# lia.net
KiCad netlist of a schematic drawn in EAGLE
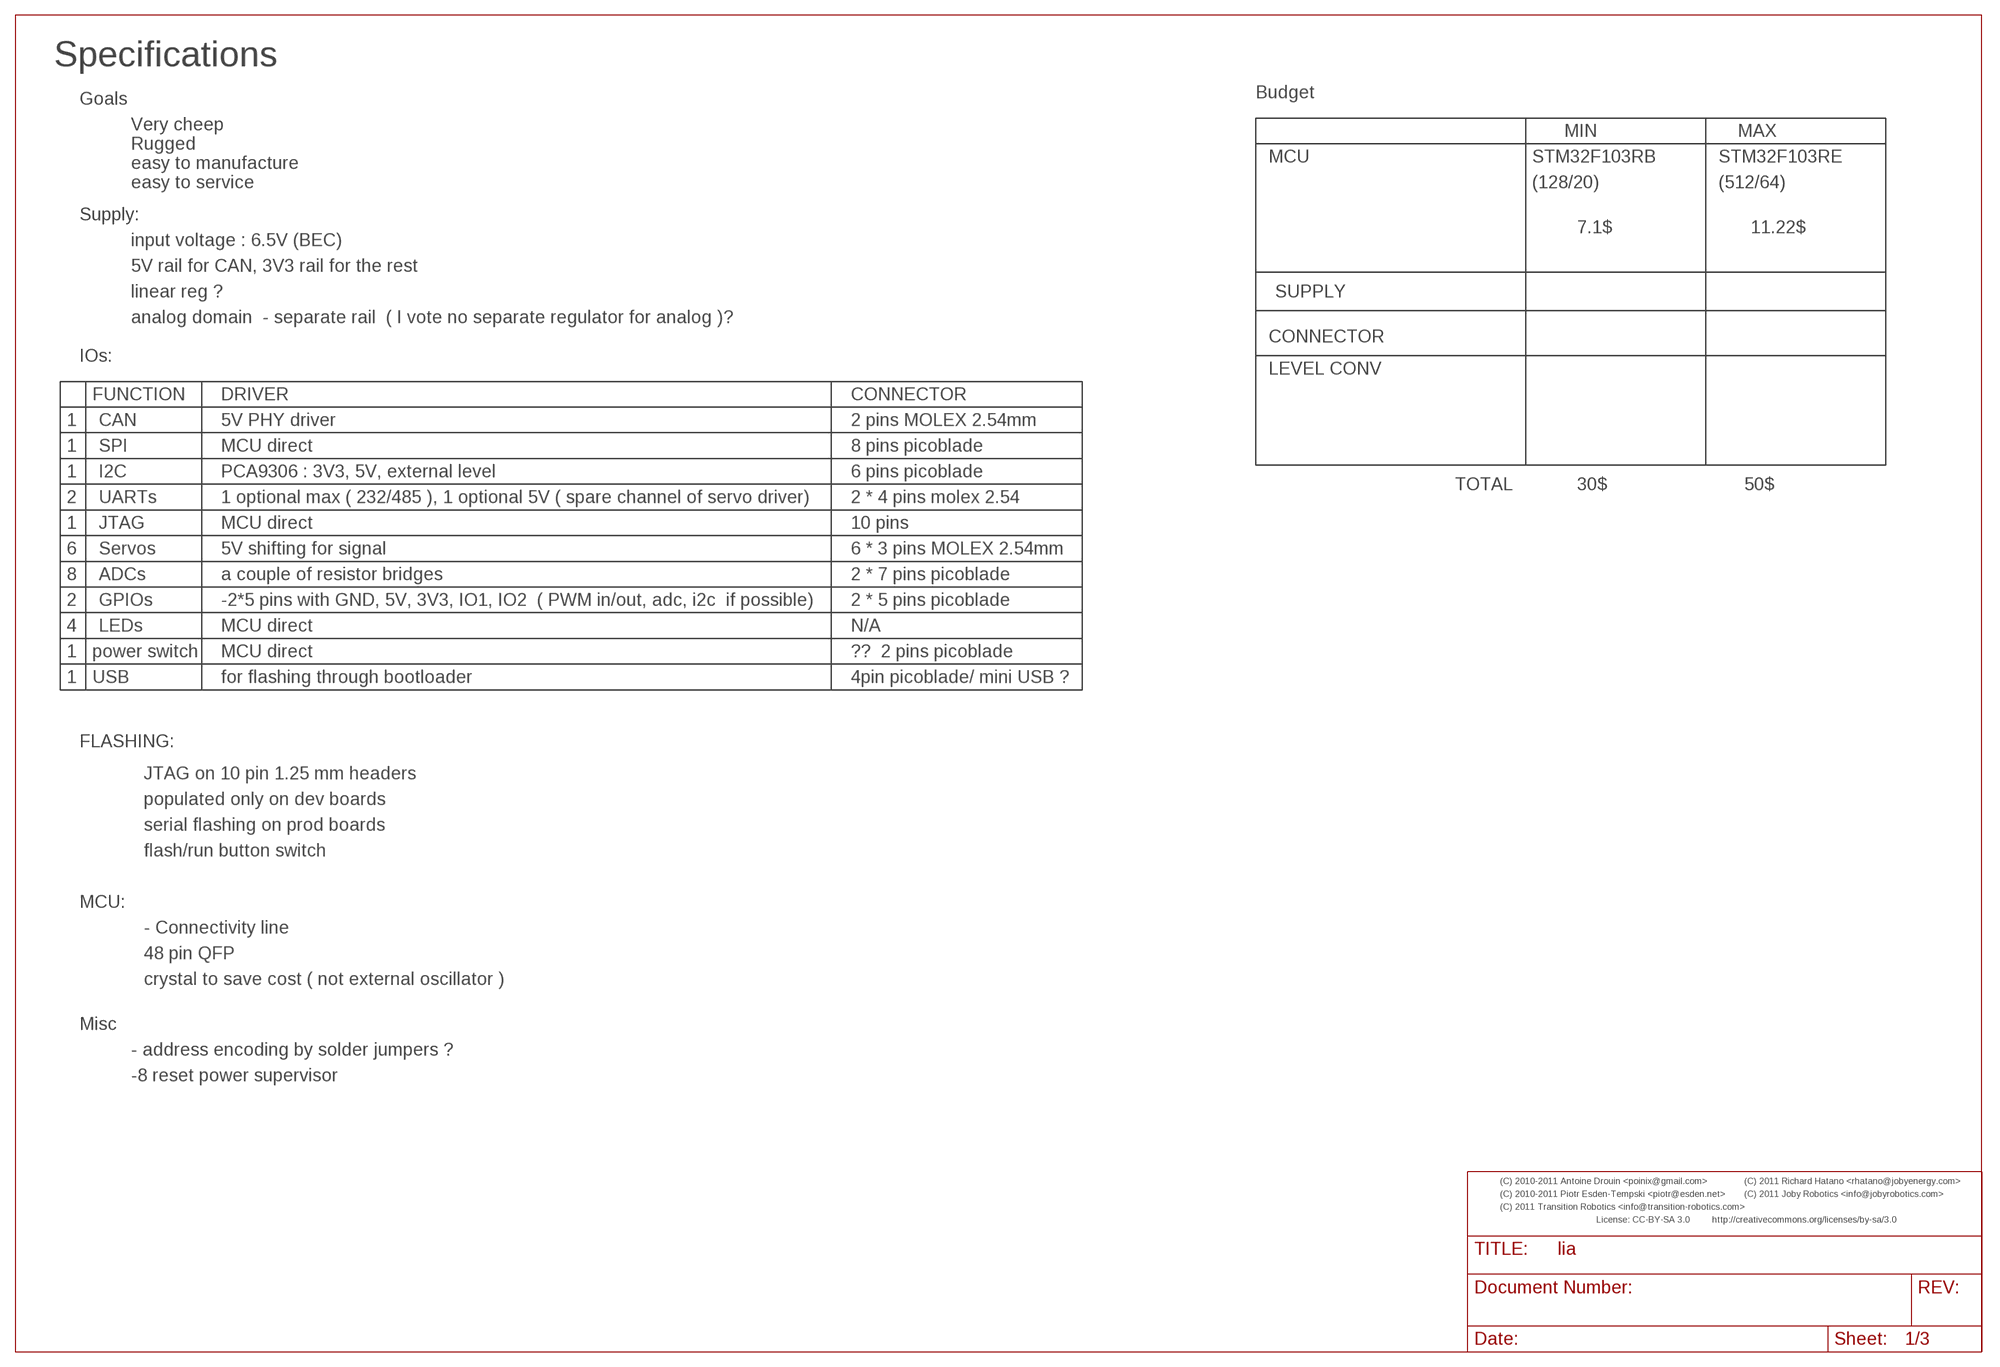
[diagram p0: schematic, sheet 1]
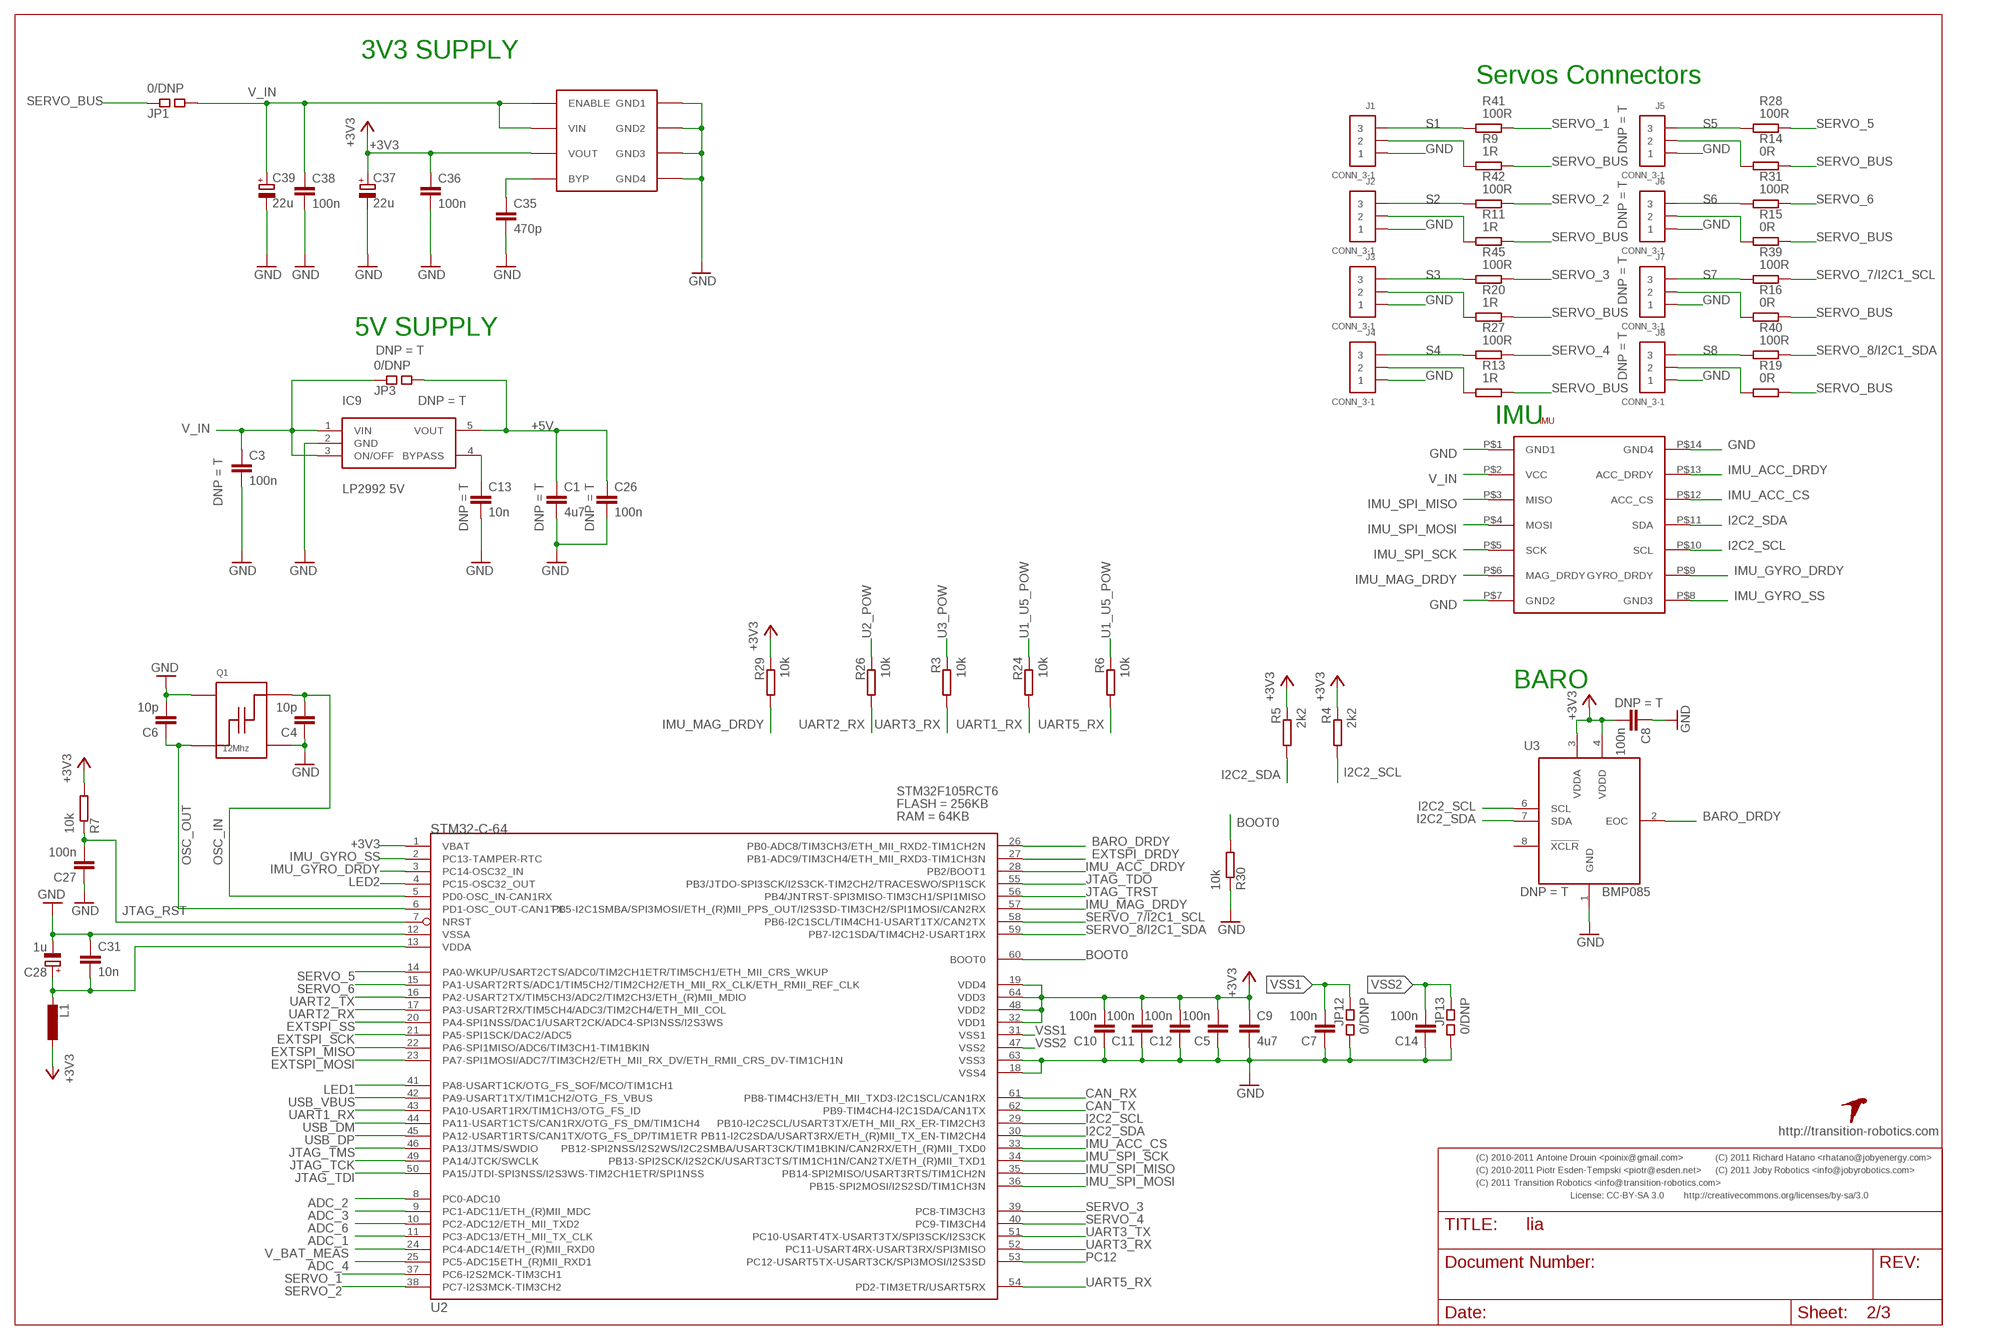
[diagram p1: schematic, sheet 2]
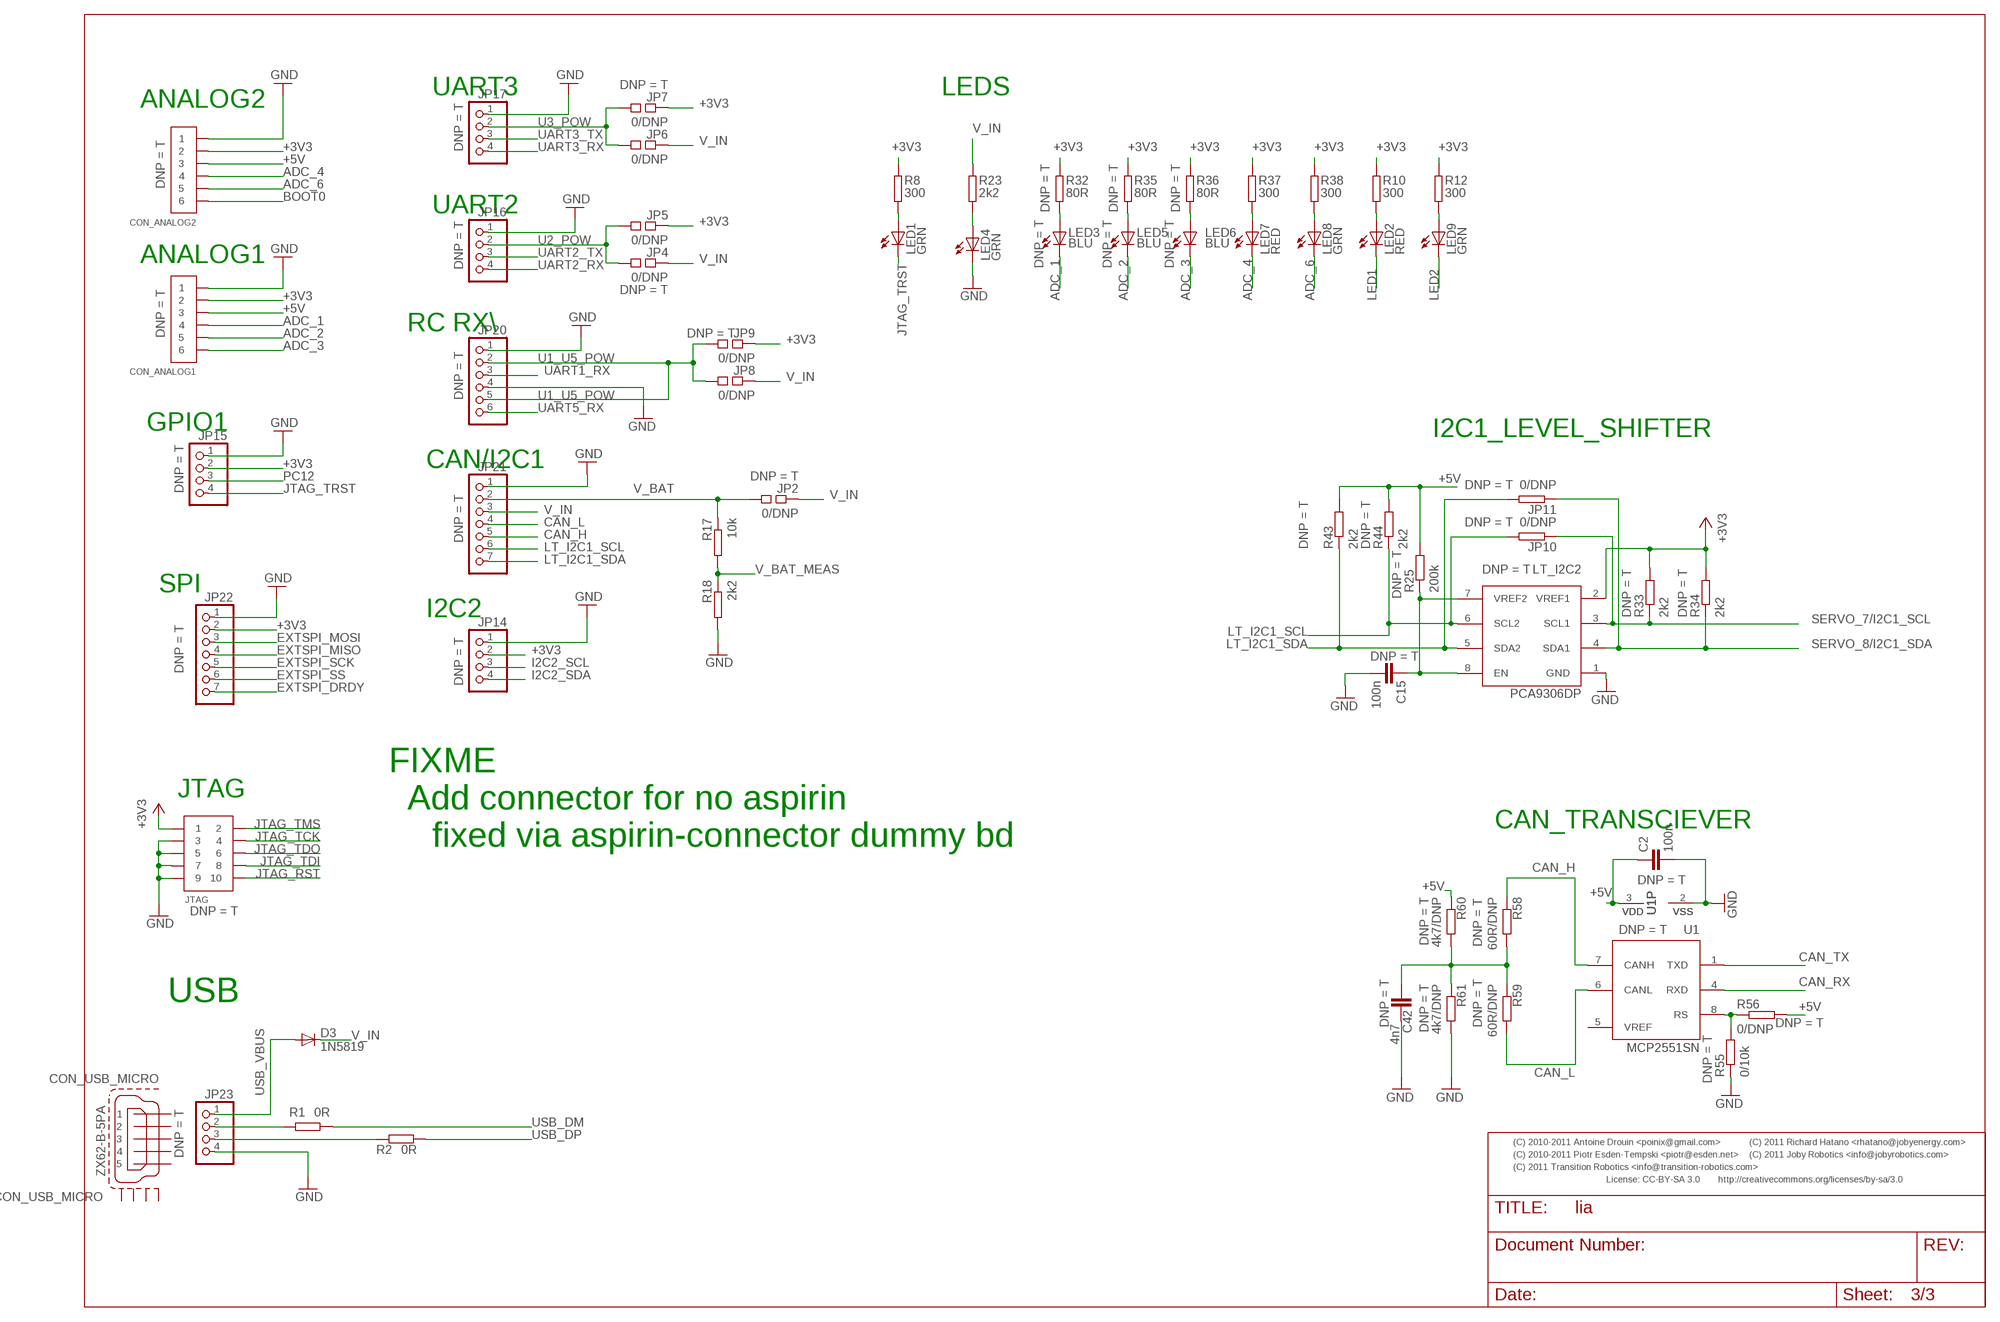
[diagram p2: schematic, sheet 3]

(export (version "E")
  (design (tool "Eeschema 10.0.6"))
  (components
    (comp (ref "C1")
      (value "4u7")
      (footprint "eagle-import:0805-CAP")
      (fields (field (name "DNP") "T") (field (name "PARTNO") "cap-cer-0805-4u7"))
      (libsource (lib "eagle-import") (part "CAPACITOR-0805"))
    )
    (comp (ref "C3")
      (value "100n")
      (footprint "eagle-import:0603-CAP")
      (fields (field (name "DNP") "T") (field (name "PARTNO") "cap-cer-0603-100n"))
      (libsource (lib "eagle-import") (part "CAPACITOR-0603"))
    )
    (comp (ref "C4")
      (value "10p")
      (footprint "eagle-import:0402-CAP")
      (fields (field (name "PARTNO") "cap-cer-0402-10p"))
      (libsource (lib "eagle-import") (part "CAPACITOR-0402"))
    )
    (comp (ref "C5")
      (value "100n")
      (footprint "eagle-import:0402-CAP")
      (fields (field (name "PARTNO") "cap-cer-0402-100n"))
      (libsource (lib "eagle-import") (part "CAPACITOR-0402"))
    )
    (comp (ref "C6")
      (value "10p")
      (footprint "eagle-import:0402-CAP")
      (fields (field (name "PARTNO") "cap-cer-0402-10p"))
      (libsource (lib "eagle-import") (part "CAPACITOR-0402"))
    )
    (comp (ref "C7")
      (value "100n")
      (footprint "eagle-import:0402-CAP")
      (fields (field (name "PARTNO") "cap-cer-0402-100n"))
      (libsource (lib "eagle-import") (part "CAPACITOR-0402"))
    )
    (comp (ref "C8")
      (value "100n")
      (footprint "eagle-import:0402-CAP")
      (fields (field (name "DNP") "T") (field (name "PARTNO") "cap-cer-0402-100n"))
      (libsource (lib "eagle-import") (part "CAPACITOR-0402"))
    )
    (comp (ref "C9")
      (value "4u7")
      (footprint "eagle-import:0805-CAP")
      (fields (field (name "PARTNO") "cap-cer-0805-4u7"))
      (libsource (lib "eagle-import") (part "CAPACITOR-0805"))
    )
    (comp (ref "C10")
      (value "100n")
      (footprint "eagle-import:0402-CAP")
      (fields (field (name "PARTNO") "cap-cer-0402-100n"))
      (libsource (lib "eagle-import") (part "CAPACITOR-0402"))
    )
    (comp (ref "C11")
      (value "100n")
      (footprint "eagle-import:0402-CAP")
      (fields (field (name "PARTNO") "cap-cer-0402-100n"))
      (libsource (lib "eagle-import") (part "CAPACITOR-0402"))
    )
    (comp (ref "C12")
      (value "100n")
      (footprint "eagle-import:0402-CAP")
      (fields (field (name "PARTNO") "cap-cer-0402-100n"))
      (libsource (lib "eagle-import") (part "CAPACITOR-0402"))
    )
    (comp (ref "C13")
      (value "10n")
      (footprint "eagle-import:0402-CAP")
      (fields (field (name "DNP") "T") (field (name "PARTNO") "cap-cer-0402-10n"))
      (libsource (lib "eagle-import") (part "CAPACITOR-0402"))
    )
    (comp (ref "C14")
      (value "100n")
      (footprint "eagle-import:0402-CAP")
      (fields (field (name "PARTNO") "cap-cer-0402-100n"))
      (libsource (lib "eagle-import") (part "CAPACITOR-0402"))
    )
    (comp (ref "C26")
      (value "100n")
      (footprint "eagle-import:0603-CAP")
      (fields (field (name "DNP") "T") (field (name "PARTNO") "cap-cer-0603-100n"))
      (libsource (lib "eagle-import") (part "CAPACITOR-0603"))
    )
    (comp (ref "C27")
      (value "100n")
      (footprint "eagle-import:0402-CAP")
      (fields (field (name "PARTNO") "cap-cer-0402-100n"))
      (libsource (lib "eagle-import") (part "CAPACITOR-0402"))
    )
    (comp (ref "C28")
      (value "1u")
      (footprint "eagle-import:0603-POL-CAP")
      (fields (field (name "PARTNO") "cap-tan-0603-1u"))
      (libsource (lib "eagle-import") (part "CAPACITOR-POL-0603"))
    )
    (comp (ref "C31")
      (value "10n")
      (footprint "eagle-import:0402-CAP")
      (fields (field (name "PARTNO") "cap-cer-0402-10n"))
      (libsource (lib "eagle-import") (part "CAPACITOR-0402"))
    )
    (comp (ref "C35")
      (value "470p")
      (footprint "eagle-import:0402-CAP")
      (fields (field (name "PARTNO") "cap-cer-0402-470p"))
      (libsource (lib "eagle-import") (part "CAPACITOR-0402"))
    )
    (comp (ref "C36")
      (value "100n")
      (footprint "eagle-import:0603-CAP")
      (fields (field (name "PARTNO") "cap-cer-0603-100n"))
      (libsource (lib "eagle-import") (part "CAPACITOR-0603"))
    )
    (comp (ref "C37")
      (value "22u")
      (footprint "eagle-import:3528_B")
      (fields (field (name "PARTNO") "cap-tan-B-22u-16v"))
      (libsource (lib "eagle-import") (part "CAPACITOR-POLB"))
    )
    (comp (ref "C38")
      (value "100n")
      (footprint "eagle-import:0402-CAP")
      (fields (field (name "PARTNO") "cap-cer-0402-100n"))
      (libsource (lib "eagle-import") (part "CAPACITOR-0402"))
    )
    (comp (ref "C39")
      (value "22u")
      (footprint "eagle-import:3528_B")
      (fields (field (name "PARTNO") "cap-tan-B-22u-16v"))
      (libsource (lib "eagle-import") (part "CAPACITOR-POLB"))
    )
    (comp (ref "IC9")
      (value "LP2992 5V")
      (footprint "eagle-import:SOT23-5")
      (fields (field (name "DNP") "T") (field (name "PARTNO") "vreg-sot-23-5-5v"))
      (libsource (lib "eagle-import") (part "LP2992"))
    )
    (comp (ref "IMU")
      (value "ASPIRIN")
      (footprint "eagle-import:ASPIRIN_1")
      (fields (field (name "PARTNO") "pcb-ass-aspirin"))
      (libsource (lib "eagle-import") (part "ASPIRIN"))
    )
    (comp (ref "J1")
      (value "CONN_3-1")
      (footprint "eagle-import:SIP1X3_100")
      (fields (field (name "PARTNO") "conn-th-0.1in-3-2-ra"))
      (libsource (lib "eagle-import") (part "CONN_3-1"))
    )
    (comp (ref "J2")
      (value "CONN_3-1")
      (footprint "eagle-import:SIP1X3_100")
      (fields (field (name "PARTNO") "conn-th-0.1in-3-2-ra"))
      (libsource (lib "eagle-import") (part "CONN_3-1"))
    )
    (comp (ref "J3")
      (value "CONN_3-1")
      (footprint "eagle-import:SIP1X3_100")
      (fields (field (name "PARTNO") "conn-th-0.1in-3-2-ra"))
      (libsource (lib "eagle-import") (part "CONN_3-1"))
    )
    (comp (ref "J4")
      (value "CONN_3-1")
      (footprint "eagle-import:SIP1X3_100")
      (fields (field (name "PARTNO") "conn-th-0.1in-3-2-ra"))
      (libsource (lib "eagle-import") (part "CONN_3-1"))
    )
    (comp (ref "J5")
      (value "CONN_3-1")
      (footprint "eagle-import:SIP1X3_100")
      (fields (field (name "DNP") "T") (field (name "PARTNO") "conn-th-0.1in-3-2-ra"))
      (libsource (lib "eagle-import") (part "CONN_3-1"))
    )
    (comp (ref "J6")
      (value "CONN_3-1")
      (footprint "eagle-import:SIP1X3_100")
      (fields (field (name "DNP") "T") (field (name "PARTNO") "conn-th-0.1in-3-2-ra"))
      (libsource (lib "eagle-import") (part "CONN_3-1"))
    )
    (comp (ref "J7")
      (value "CONN_3-1")
      (footprint "eagle-import:SIP1X3_100")
      (fields (field (name "DNP") "T") (field (name "PARTNO") "conn-th-0.1in-3-2-ra"))
      (libsource (lib "eagle-import") (part "CONN_3-1"))
    )
    (comp (ref "J8")
      (value "CONN_3-1")
      (footprint "eagle-import:SIP1X3_100")
      (fields (field (name "DNP") "T") (field (name "PARTNO") "conn-th-0.1in-3-2-ra"))
      (libsource (lib "eagle-import") (part "CONN_3-1"))
    )
    (comp (ref "JP1")
      (value "0/DNP")
      (footprint "eagle-import:0402-SQJMP")
      (fields (field (name "PARTNO") "res-0402-0"))
      (libsource (lib "eagle-import") (part "SQ_JMP-0402"))
    )
    (comp (ref "JP3")
      (value "0/DNP")
      (footprint "eagle-import:0402-SQJMP")
      (fields (field (name "DNP") "T") (field (name "PARTNO") "res-0402-0"))
      (libsource (lib "eagle-import") (part "SQ_JMP-0402"))
    )
    (comp (ref "JP12")
      (value "0/DNP")
      (footprint "eagle-import:0402-SQJMP")
      (fields (field (name "PARTNO") "res-0402-0"))
      (libsource (lib "eagle-import") (part "SQ_JMP-0402"))
    )
    (comp (ref "JP13")
      (value "0/DNP")
      (footprint "eagle-import:0402-SQJMP")
      (fields (field (name "PARTNO") "res-0402-0"))
      (libsource (lib "eagle-import") (part "SQ_JMP-0402"))
    )
    (comp (ref "L1")
      (value "INDUCTOR-0603")
      (footprint "eagle-import:0603-IND")
      (fields (field (name "PARTNO") "ferrite-0603-600ohm"))
      (libsource (lib "eagle-import") (part "INDUCTOR-0603"))
    )
    (comp (ref "Q1")
      (value "12Mhz")
      (footprint "eagle-import:ABM8")
      (fields (field (name "PARTNO") "xtal-abm8-12mhz"))
      (libsource (lib "eagle-import") (part "ABM8"))
    )
    (comp (ref "R3")
      (value "10k")
      (footprint "eagle-import:0402-RES")
      (fields (field (name "PARTNO") "res-0402-10k"))
      (libsource (lib "eagle-import") (part "RESISTOR-0402"))
    )
    (comp (ref "R4")
      (value "2k2")
      (footprint "eagle-import:0402-RES")
      (fields (field (name "PARTNO") "res-0402-2k2"))
      (libsource (lib "eagle-import") (part "RESISTOR-0402"))
    )
    (comp (ref "R5")
      (value "2k2")
      (footprint "eagle-import:0402-RES")
      (fields (field (name "PARTNO") "res-0402-2k2"))
      (libsource (lib "eagle-import") (part "RESISTOR-0402"))
    )
    (comp (ref "R6")
      (value "10k")
      (footprint "eagle-import:0402-RES")
      (fields (field (name "PARTNO") "res-0402-10k"))
      (libsource (lib "eagle-import") (part "RESISTOR-0402"))
    )
    (comp (ref "R7")
      (value "10k")
      (footprint "eagle-import:0402-RES")
      (fields (field (name "PARTNO") "res-0402-10k"))
      (libsource (lib "eagle-import") (part "RESISTOR-0402"))
    )
    (comp (ref "R9")
      (value "1R")
      (footprint "eagle-import:1206-RES")
      (fields (field (name "PARTNO") "res-1206-1"))
      (libsource (lib "eagle-import") (part "RESISTOR-1206"))
    )
    (comp (ref "R11")
      (value "1R")
      (footprint "eagle-import:1206-RES")
      (fields (field (name "PARTNO") "res-1206-1"))
      (libsource (lib "eagle-import") (part "RESISTOR-1206"))
    )
    (comp (ref "R13")
      (value "1R")
      (footprint "eagle-import:1206-RES")
      (fields (field (name "PARTNO") "res-1206-1"))
      (libsource (lib "eagle-import") (part "RESISTOR-1206"))
    )
    (comp (ref "R14")
      (value "0R")
      (footprint "eagle-import:1206-RES")
      (fields (field (name "PARTNO") "res-1206-0"))
      (libsource (lib "eagle-import") (part "RESISTOR-1206"))
    )
    (comp (ref "R15")
      (value "0R")
      (footprint "eagle-import:1206-RES")
      (fields (field (name "PARTNO") "res-1206-0"))
      (libsource (lib "eagle-import") (part "RESISTOR-1206"))
    )
    (comp (ref "R16")
      (value "0R")
      (footprint "eagle-import:1206-RES")
      (fields (field (name "PARTNO") "res-1206-0"))
      (libsource (lib "eagle-import") (part "RESISTOR-1206"))
    )
    (comp (ref "R19")
      (value "0R")
      (footprint "eagle-import:1206-RES")
      (fields (field (name "PARTNO") "res-1206-0"))
      (libsource (lib "eagle-import") (part "RESISTOR-1206"))
    )
    (comp (ref "R20")
      (value "1R")
      (footprint "eagle-import:1206-RES")
      (fields (field (name "PARTNO") "res-1206-1"))
      (libsource (lib "eagle-import") (part "RESISTOR-1206"))
    )
    (comp (ref "R24")
      (value "10k")
      (footprint "eagle-import:0402-RES")
      (fields (field (name "PARTNO") "res-0402-10k"))
      (libsource (lib "eagle-import") (part "RESISTOR-0402"))
    )
    (comp (ref "R26")
      (value "10k")
      (footprint "eagle-import:0402-RES")
      (fields (field (name "PARTNO") "res-0402-10k"))
      (libsource (lib "eagle-import") (part "RESISTOR-0402"))
    )
    (comp (ref "R27")
      (value "100R")
      (footprint "eagle-import:0402-RES")
      (fields (field (name "PARTNO") "res-0402-100"))
      (libsource (lib "eagle-import") (part "RESISTOR-0402"))
    )
    (comp (ref "R28")
      (value "100R")
      (footprint "eagle-import:0402-RES")
      (fields (field (name "PARTNO") "res-0402-100"))
      (libsource (lib "eagle-import") (part "RESISTOR-0402"))
    )
    (comp (ref "R29")
      (value "10k")
      (footprint "eagle-import:0402-RES")
      (fields (field (name "PARTNO") "res-0402-10k"))
      (libsource (lib "eagle-import") (part "RESISTOR-0402"))
    )
    (comp (ref "R30")
      (value "10k")
      (footprint "eagle-import:0402-RES")
      (fields (field (name "PARTNO") "res-0402-10k"))
      (libsource (lib "eagle-import") (part "RESISTOR-0402"))
    )
    (comp (ref "R31")
      (value "100R")
      (footprint "eagle-import:0402-RES")
      (fields (field (name "PARTNO") "res-0402-100"))
      (libsource (lib "eagle-import") (part "RESISTOR-0402"))
    )
    (comp (ref "R39")
      (value "100R")
      (footprint "eagle-import:0402-RES")
      (fields (field (name "PARTNO") "res-0402-100"))
      (libsource (lib "eagle-import") (part "RESISTOR-0402"))
    )
    (comp (ref "R40")
      (value "100R")
      (footprint "eagle-import:0402-RES")
      (fields (field (name "PARTNO") "res-0402-100"))
      (libsource (lib "eagle-import") (part "RESISTOR-0402"))
    )
    (comp (ref "R41")
      (value "100R")
      (footprint "eagle-import:0402-RES")
      (fields (field (name "PARTNO") "res-0402-100"))
      (libsource (lib "eagle-import") (part "RESISTOR-0402"))
    )
    (comp (ref "R42")
      (value "100R")
      (footprint "eagle-import:0402-RES")
      (fields (field (name "PARTNO") "res-0402-100"))
      (libsource (lib "eagle-import") (part "RESISTOR-0402"))
    )
    (comp (ref "R45")
      (value "100R")
      (footprint "eagle-import:0402-RES")
      (fields (field (name "PARTNO") "res-0402-100"))
      (libsource (lib "eagle-import") (part "RESISTOR-0402"))
    )
    (comp (ref "U$1")
      (value "TR-LOGO")
      (footprint "eagle-import:TR-LOGO")
      (libsource (lib "eagle-import") (part "TR-LOGO"))
    )
    (comp (ref "U2")
      (value "STM32-C-64")
      (footprint "eagle-import:LQFP64")
      (fields
        (field (name "FLASH") "256KB")
        (field (name "PARTNO") "mcu-lqfp-64-stm32")
        (field (name "PART_NR") "STM32F105RCT6")
        (field (name "RAM") "64KB")
      )
      (libsource (lib "eagle-import") (part "STM32-C-64"))
    )
    (comp (ref "U3")
      (value "BMP085")
      (footprint "eagle-import:LCC8")
      (fields (field (name "DNP") "T") (field (name "PARTNO") "sensr-clcc-8-baro"))
      (libsource (lib "eagle-import") (part "BMP085"))
    )
    (comp (ref "VREG1")
      (value "MIC5209")
      (footprint "eagle-import:SOIC8")
      (fields (field (name "PARTNO") "vreg-so8-3v3"))
      (libsource (lib "eagle-import") (part "MIC5209"))
    )
    (comp (ref "C2")
      (value "100n")
      (footprint "eagle-import:0402-CAP")
      (fields (field (name "DNP") "T") (field (name "PARTNO") "cap-cer-0402-100n"))
      (libsource (lib "eagle-import") (part "CAPACITOR-0402"))
    )
    (comp (ref "C15")
      (value "100n")
      (footprint "eagle-import:0402-CAP")
      (fields (field (name "DNP") "T") (field (name "PARTNO") "cap-cer-0402-100n"))
      (libsource (lib "eagle-import") (part "CAPACITOR-0402"))
    )
    (comp (ref "C42")
      (value "4n7")
      (footprint "eagle-import:0603-CAP")
      (fields (field (name "DNP") "T") (field (name "PARTNO") "cap-cer-0603-4n7"))
      (libsource (lib "eagle-import") (part "CAPACITOR-0603"))
    )
    (comp (ref "CON_ANALOG1")
      (value "CONN_6-1-53398")
      (footprint "eagle-import:PB-53398-06")
      (fields (field (name "DNP") "T") (field (name "PARTNO") "conn-picoblade-smd-0.05in-6-vert"))
      (libsource (lib "eagle-import") (part "CONN_6-1-53398"))
    )
    (comp (ref "CON_ANALOG2")
      (value "CONN_6-1-53398")
      (footprint "eagle-import:PB-53398-06")
      (fields (field (name "DNP") "T") (field (name "PARTNO") "conn-picoblade-smd-0.05in-6-vert"))
      (libsource (lib "eagle-import") (part "CONN_6-1-53398"))
    )
    (comp (ref "CON_USB_MICRO")
      (value "ZX62-B-5PA")
      (footprint "eagle-import:ZX62-B-5PA")
      (fields (field (name "PARTNO") "conn-smd-usb-micro-b"))
      (libsource (lib "eagle-import") (part "ZX62-B-5PA"))
    )
    (comp (ref "D3")
      (value "1N5819")
      (footprint "eagle-import:MICROMELF-R")
      (fields (field (name "PARTNO") "diode-schottky-1608"))
      (libsource (lib "eagle-import") (part "DIODE-MICROMELF-R"))
    )
    (comp (ref "JP2")
      (value "0/DNP")
      (footprint "eagle-import:0402-SQJMP")
      (fields (field (name "DNP") "T") (field (name "PARTNO") "res-0402-0"))
      (libsource (lib "eagle-import") (part "SQ_JMP-0402"))
    )
    (comp (ref "JP4")
      (value "0/DNP")
      (footprint "eagle-import:0402-SQJMP")
      (fields (field (name "DNP") "T") (field (name "PARTNO") "res-0402-0"))
      (libsource (lib "eagle-import") (part "SQ_JMP-0402"))
    )
    (comp (ref "JP5")
      (value "0/DNP")
      (footprint "eagle-import:0402-SQJMP")
      (fields (field (name "PARTNO") "res-0402-0"))
      (libsource (lib "eagle-import") (part "SQ_JMP-0402"))
    )
    (comp (ref "JP6")
      (value "0/DNP")
      (footprint "eagle-import:0402-SQJMP")
      (fields (field (name "PARTNO") "res-0402-0"))
      (libsource (lib "eagle-import") (part "SQ_JMP-0402"))
    )
    (comp (ref "JP7")
      (value "0/DNP")
      (footprint "eagle-import:0402-SQJMP")
      (fields (field (name "DNP") "T") (field (name "PARTNO") "res-0402-0"))
      (libsource (lib "eagle-import") (part "SQ_JMP-0402"))
    )
    (comp (ref "JP8")
      (value "0/DNP")
      (footprint "eagle-import:0402-SQJMP")
      (fields (field (name "PARTNO") "res-0402-0"))
      (libsource (lib "eagle-import") (part "SQ_JMP-0402"))
    )
    (comp (ref "JP9")
      (value "0/DNP")
      (footprint "eagle-import:0402-SQJMP")
      (fields (field (name "DNP") "T") (field (name "PARTNO") "res-0402-0"))
      (libsource (lib "eagle-import") (part "SQ_JMP-0402"))
    )
    (comp (ref "JP10")
      (value "0/DNP")
      (footprint "eagle-import:0603-RES")
      (fields (field (name "DNP") "T") (field (name "PARTNO") "res-0603-0"))
      (libsource (lib "eagle-import") (part "RESISTOR-0603"))
    )
    (comp (ref "JP11")
      (value "0/DNP")
      (footprint "eagle-import:0603-RES")
      (fields (field (name "DNP") "T") (field (name "PARTNO") "res-0603-0"))
      (libsource (lib "eagle-import") (part "RESISTOR-0603"))
    )
    (comp (ref "JP14")
      (value "PINHD-1X4")
      (footprint "eagle-import:1X04")
      (fields (field (name "DNP") "T") (field (name "PARTNO") "conn-th-0.1in-4-1"))
      (libsource (lib "eagle-import") (part "PINHD-1X4"))
    )
    (comp (ref "JP15")
      (value "PINHD-1X4")
      (footprint "eagle-import:1X04")
      (fields (field (name "DNP") "T") (field (name "PARTNO") "conn-th-0.1in-4-1"))
      (libsource (lib "eagle-import") (part "PINHD-1X4"))
    )
    (comp (ref "JP16")
      (value "PINHD-1X4")
      (footprint "eagle-import:1X04")
      (fields (field (name "DNP") "T") (field (name "PARTNO") "conn-th-0.1in-4-1"))
      (libsource (lib "eagle-import") (part "PINHD-1X4"))
    )
    (comp (ref "JP17")
      (value "PINHD-1X4")
      (footprint "eagle-import:1X04")
      (fields (field (name "DNP") "T") (field (name "PARTNO") "conn-th-0.1in-4-1"))
      (libsource (lib "eagle-import") (part "PINHD-1X4"))
    )
    (comp (ref "JP20")
      (value "PINHD-1X6")
      (footprint "eagle-import:1X06")
      (fields (field (name "DNP") "T") (field (name "PARTNO") "conn-th-0.1in-6-1"))
      (libsource (lib "eagle-import") (part "PINHD-1X6"))
    )
    (comp (ref "JP21")
      (value "PINHD-1X7")
      (footprint "eagle-import:1X07")
      (fields (field (name "DNP") "T") (field (name "PARTNO") "conn-th-0.1in-7-1"))
      (libsource (lib "eagle-import") (part "PINHD-1X7"))
    )
    (comp (ref "JP22")
      (value "PINHD-1X7")
      (footprint "eagle-import:1X07")
      (fields (field (name "DNP") "T") (field (name "PARTNO") "conn-th-0.1in-7-1"))
      (libsource (lib "eagle-import") (part "PINHD-1X7"))
    )
    (comp (ref "JP23")
      (value "PINHD-1X4")
      (footprint "eagle-import:1X04")
      (fields (field (name "DNP") "T") (field (name "PARTNO") "conn-th-0.1in-4-1"))
      (libsource (lib "eagle-import") (part "PINHD-1X4"))
    )
    (comp (ref "JTAG")
      (value "PIN_HDR_EDG_1.27MM_5-2")
      (footprint "eagle-import:FTSH-105-DV")
      (fields (field (name "DNP") "T") (field (name "PARTNO") "conn-smd-0.05in-5-2"))
      (libsource (lib "eagle-import") (part "CONN_5-2-FTSH-V"))
    )
    (comp (ref "LED1")
      (value "GRN")
      (footprint "eagle-import:0402-LED")
      (fields (field (name "PARTNO") "led-0402-green"))
      (libsource (lib "eagle-import") (part "LED-0402"))
    )
    (comp (ref "LED2")
      (value "RED")
      (footprint "eagle-import:0402-LED")
      (fields (field (name "PARTNO") "led-0402-red"))
      (libsource (lib "eagle-import") (part "LED-0402"))
    )
    (comp (ref "LED3")
      (value "BLU")
      (footprint "eagle-import:0402-LED")
      (fields (field (name "DNP") "T") (field (name "PARTNO") "led-0402-blue"))
      (libsource (lib "eagle-import") (part "LED-0402"))
    )
    (comp (ref "LED4")
      (value "GRN")
      (footprint "eagle-import:0402-LED")
      (fields (field (name "PARTNO") "led-0402-green"))
      (libsource (lib "eagle-import") (part "LED-0402"))
    )
    (comp (ref "LED5")
      (value "BLU")
      (footprint "eagle-import:0402-LED")
      (fields (field (name "DNP") "T") (field (name "PARTNO") "led-0402-blue"))
      (libsource (lib "eagle-import") (part "LED-0402"))
    )
    (comp (ref "LED6")
      (value "BLU")
      (footprint "eagle-import:0402-LED")
      (fields (field (name "DNP") "T") (field (name "PARTNO") "led-0402-blue"))
      (libsource (lib "eagle-import") (part "LED-0402"))
    )
    (comp (ref "LED7")
      (value "RED")
      (footprint "eagle-import:0402-LED")
      (fields (field (name "PARTNO") "led-0402-red"))
      (libsource (lib "eagle-import") (part "LED-0402"))
    )
    (comp (ref "LED8")
      (value "GRN")
      (footprint "eagle-import:0402-LED")
      (fields (field (name "PARTNO") "led-0402-green"))
      (libsource (lib "eagle-import") (part "LED-0402"))
    )
    (comp (ref "LED9")
      (value "GRN")
      (footprint "eagle-import:0402-LED")
      (fields (field (name "PARTNO") "led-0402-green"))
      (libsource (lib "eagle-import") (part "LED-0402"))
    )
    (comp (ref "LT_I2C2")
      (value "PCA9306DP")
      (footprint "eagle-import:TSSOP_B3")
      (fields (field (name "DNP") "T") (field (name "PARTNO") "ic-tssop8-level-trans"))
      (libsource (lib "eagle-import") (part "PCA9306DP"))
    )
    (comp (ref "R1")
      (value "0R")
      (footprint "eagle-import:0402-RES")
      (fields (field (name "PARTNO") "res-0402-0"))
      (libsource (lib "eagle-import") (part "RESISTOR-0402"))
    )
    (comp (ref "R2")
      (value "0R")
      (footprint "eagle-import:0402-RES")
      (fields (field (name "PARTNO") "res-0402-0"))
      (libsource (lib "eagle-import") (part "RESISTOR-0402"))
    )
    (comp (ref "R8")
      (value "300")
      (footprint "eagle-import:0402-RES")
      (fields (field (name "PARTNO") "res-0402-300"))
      (libsource (lib "eagle-import") (part "RESISTOR-0402"))
    )
    (comp (ref "R10")
      (value "300")
      (footprint "eagle-import:0402-RES")
      (fields (field (name "PARTNO") "res-0402-300"))
      (libsource (lib "eagle-import") (part "RESISTOR-0402"))
    )
    (comp (ref "R12")
      (value "300")
      (footprint "eagle-import:0402-RES")
      (fields (field (name "PARTNO") "res-0402-300"))
      (libsource (lib "eagle-import") (part "RESISTOR-0402"))
    )
    (comp (ref "R17")
      (value "10k")
      (footprint "eagle-import:0402-RES")
      (fields (field (name "PARTNO") "res-0402-10k"))
      (libsource (lib "eagle-import") (part "RESISTOR-0402"))
    )
    (comp (ref "R18")
      (value "2k2")
      (footprint "eagle-import:0402-RES")
      (fields (field (name "PARTNO") "res-0402-2k2"))
      (libsource (lib "eagle-import") (part "RESISTOR-0402"))
    )
    (comp (ref "R23")
      (value "2k2")
      (footprint "eagle-import:0402-RES")
      (fields (field (name "PARTNO") "res-0402-2k2"))
      (libsource (lib "eagle-import") (part "RESISTOR-0402"))
    )
    (comp (ref "R25")
      (value "200k")
      (footprint "eagle-import:0402-RES")
      (fields (field (name "DNP") "T") (field (name "PARTNO") "res-0402-200k"))
      (libsource (lib "eagle-import") (part "RESISTOR-0402"))
    )
    (comp (ref "R32")
      (value "80R")
      (footprint "eagle-import:0402-RES")
      (fields (field (name "DNP") "T") (field (name "PARTNO") "res-0402-80"))
      (libsource (lib "eagle-import") (part "RESISTOR-0402"))
    )
    (comp (ref "R33")
      (value "2k2")
      (footprint "eagle-import:0402-RES")
      (fields (field (name "DNP") "T") (field (name "PARTNO") "res-0402-2k2"))
      (libsource (lib "eagle-import") (part "RESISTOR-0402"))
    )
    (comp (ref "R34")
      (value "2k2")
      (footprint "eagle-import:0402-RES")
      (fields (field (name "DNP") "T") (field (name "PARTNO") "res-0402-2k2"))
      (libsource (lib "eagle-import") (part "RESISTOR-0402"))
    )
    (comp (ref "R35")
      (value "80R")
      (footprint "eagle-import:0402-RES")
      (fields (field (name "DNP") "T") (field (name "PARTNO") "res-0402-80"))
      (libsource (lib "eagle-import") (part "RESISTOR-0402"))
    )
    (comp (ref "R36")
      (value "80R")
      (footprint "eagle-import:0402-RES")
      (fields (field (name "DNP") "T") (field (name "PARTNO") "res-0402-80"))
      (libsource (lib "eagle-import") (part "RESISTOR-0402"))
    )
    (comp (ref "R37")
      (value "300")
      (footprint "eagle-import:0402-RES")
      (fields (field (name "PARTNO") "res-0402-300"))
      (libsource (lib "eagle-import") (part "RESISTOR-0402"))
    )
    (comp (ref "R38")
      (value "300")
      (footprint "eagle-import:0402-RES")
      (fields (field (name "PARTNO") "res-0402-300"))
      (libsource (lib "eagle-import") (part "RESISTOR-0402"))
    )
    (comp (ref "R43")
      (value "2k2")
      (footprint "eagle-import:0402-RES")
      (fields (field (name "DNP") "T") (field (name "PARTNO") "res-0402-1k5"))
      (libsource (lib "eagle-import") (part "RESISTOR-0402"))
    )
    (comp (ref "R44")
      (value "2k2")
      (footprint "eagle-import:0402-RES")
      (fields (field (name "DNP") "T") (field (name "PARTNO") "res-0402-1k5"))
      (libsource (lib "eagle-import") (part "RESISTOR-0402"))
    )
    (comp (ref "R55")
      (value "0/10k")
      (footprint "eagle-import:0402-RES")
      (fields (field (name "DNP") "T") (field (name "PARTNO") "res-0402-10k"))
      (libsource (lib "eagle-import") (part "RESISTOR-0402"))
    )
    (comp (ref "R56")
      (value "0/DNP")
      (footprint "eagle-import:0402-RES")
      (fields (field (name "DNP") "T") (field (name "PARTNO") "res-0402-0"))
      (libsource (lib "eagle-import") (part "RESISTOR-0402"))
    )
    (comp (ref "R58")
      (value "60R/DNP")
      (footprint "eagle-import:0402-RES")
      (fields (field (name "DNP") "T") (field (name "PARTNO") "res-0402-60.4"))
      (libsource (lib "eagle-import") (part "RESISTOR-0402"))
    )
    (comp (ref "R59")
      (value "60R/DNP")
      (footprint "eagle-import:0402-RES")
      (fields (field (name "DNP") "T") (field (name "PARTNO") "res-0402-60.4"))
      (libsource (lib "eagle-import") (part "RESISTOR-0402"))
    )
    (comp (ref "R60")
      (value "4k7/DNP")
      (footprint "eagle-import:0402-RES")
      (fields (field (name "DNP") "T") (field (name "PARTNO") "res-0402-4k7"))
      (libsource (lib "eagle-import") (part "RESISTOR-0402"))
    )
    (comp (ref "R61")
      (value "4k7/DNP")
      (footprint "eagle-import:0402-RES")
      (fields (field (name "DNP") "T") (field (name "PARTNO") "res-0402-4k7"))
      (libsource (lib "eagle-import") (part "RESISTOR-0402"))
    )
    (comp (ref "U1")
      (value "MCP2551SN")
      (footprint "eagle-import:SO-08")
      (fields (field (name "DNP") "T") (field (name "PARTNO") "ic-so8-can"))
      (libsource (lib "eagle-import") (part "MCP2551SN"))
    )
  )
  (nets
    (net (code "1") (name "+3V3") (class "Default")
      (node (ref "C10") (pin "P$2") (pinfunction "2_P$2") (pintype "passive"))
      (node (ref "C11") (pin "P$2") (pinfunction "2_P$2") (pintype "passive"))
      (node (ref "C12") (pin "P$2") (pinfunction "2_P$2") (pintype "passive"))
      (node (ref "C36") (pin "P$1") (pinfunction "1_P$1") (pintype "passive"))
      (node (ref "C37") (pin "+") (pinfunction "+_+") (pintype "passive"))
      (node (ref "C5") (pin "P$2") (pinfunction "2_P$2") (pintype "passive"))
      (node (ref "C8") (pin "P$2") (pinfunction "2_P$2") (pintype "passive"))
      (node (ref "C9") (pin "P$1") (pinfunction "1_P$1") (pintype "passive"))
      (node (ref "CON_ANALOG1") (pin "2") (pinfunction "2_2") (pintype "bidirectional"))
      (node (ref "CON_ANALOG2") (pin "2") (pinfunction "2_2") (pintype "bidirectional"))
      (node (ref "JP14") (pin "2") (pinfunction "2_2") (pintype "passive"))
      (node (ref "JP15") (pin "2") (pinfunction "2_2") (pintype "passive"))
      (node (ref "JP22") (pin "2") (pinfunction "2_2") (pintype "passive"))
      (node (ref "JP5") (pin "P$1") (pinfunction "1_P$1") (pintype "passive"))
      (node (ref "JP7") (pin "P$1") (pinfunction "1_P$1") (pintype "passive"))
      (node (ref "JP9") (pin "P$1") (pinfunction "1_P$1") (pintype "passive"))
      (node (ref "JTAG") (pin "1") (pinfunction "1_1") (pintype "bidirectional"))
      (node (ref "L1") (pin "P$1") (pinfunction "1_P$1") (pintype "passive"))
      (node (ref "LT_I2C2") (pin "2") (pinfunction "VREF1_2") (pintype "bidirectional"))
      (node (ref "R10") (pin "P$2") (pinfunction "2_P$2") (pintype "passive"))
      (node (ref "R12") (pin "P$2") (pinfunction "2_P$2") (pintype "passive"))
      (node (ref "R29") (pin "P$1") (pinfunction "1_P$1") (pintype "passive"))
      (node (ref "R32") (pin "P$2") (pinfunction "2_P$2") (pintype "passive"))
      (node (ref "R33") (pin "P$2") (pinfunction "2_P$2") (pintype "passive"))
      (node (ref "R34") (pin "P$2") (pinfunction "2_P$2") (pintype "passive"))
      (node (ref "R35") (pin "P$2") (pinfunction "2_P$2") (pintype "passive"))
      (node (ref "R36") (pin "P$2") (pinfunction "2_P$2") (pintype "passive"))
      (node (ref "R37") (pin "P$2") (pinfunction "2_P$2") (pintype "passive"))
      (node (ref "R38") (pin "P$2") (pinfunction "2_P$2") (pintype "passive"))
      (node (ref "R4") (pin "P$1") (pinfunction "1_P$1") (pintype "passive"))
      (node (ref "R5") (pin "P$1") (pinfunction "1_P$1") (pintype "passive"))
      (node (ref "R7") (pin "P$2") (pinfunction "2_P$2") (pintype "passive"))
      (node (ref "R8") (pin "P$2") (pinfunction "2_P$2") (pintype "passive"))
      (node (ref "U2") (pin "1") (pinfunction "VBAT_1") (pintype "power_in"))
      (node (ref "U2") (pin "19") (pinfunction "VDD4_19") (pintype "bidirectional"))
      (node (ref "U2") (pin "32") (pinfunction "VDD1_32") (pintype "power_in"))
      (node (ref "U2") (pin "48") (pinfunction "VDD2_48") (pintype "power_in"))
      (node (ref "U2") (pin "64") (pinfunction "VDD3_64") (pintype "power_in"))
      (node (ref "U3") (pin "3") (pinfunction "VDDA_3") (pintype "power_in"))
      (node (ref "U3") (pin "4") (pinfunction "VDDD_4") (pintype "power_in"))
      (node (ref "VREG1") (pin "3") (pinfunction "VOUT_3") (pintype "bidirectional"))
    )
    (net (code "2") (name "+5V") (class "Default")
      (node (ref "C1") (pin "P$1") (pinfunction "1_P$1") (pintype "passive"))
      (node (ref "C2") (pin "P$1") (pinfunction "1_P$1") (pintype "passive"))
      (node (ref "C26") (pin "P$1") (pinfunction "1_P$1") (pintype "passive"))
      (node (ref "CON_ANALOG1") (pin "3") (pinfunction "3_3") (pintype "bidirectional"))
      (node (ref "CON_ANALOG2") (pin "3") (pinfunction "3_3") (pintype "bidirectional"))
      (node (ref "IC9") (pin "5") (pinfunction "VOUT_5") (pintype "bidirectional"))
      (node (ref "JP3") (pin "P$2") (pinfunction "2_P$2") (pintype "passive"))
      (node (ref "R25") (pin "P$2") (pinfunction "2_P$2") (pintype "passive"))
      (node (ref "R43") (pin "P$2") (pinfunction "2_P$2") (pintype "passive"))
      (node (ref "R44") (pin "P$2") (pinfunction "2_P$2") (pintype "passive"))
      (node (ref "R56") (pin "P$2") (pinfunction "2_P$2") (pintype "passive"))
      (node (ref "R60") (pin "P$1") (pinfunction "1_P$1") (pintype "passive"))
      (node (ref "U1") (pin "3") (pinfunction "VDD_3") (pintype "power_in"))
    )
    (net (code "3") (name "ADC_1") (class "Default")
      (node (ref "CON_ANALOG1") (pin "4") (pinfunction "4_4") (pintype "bidirectional"))
      (node (ref "LED3") (pin "C") (pinfunction "C_C") (pintype "passive"))
      (node (ref "U2") (pin "11") (pinfunction "PC3-ADC13/ETH_MII_TX_CLK_11") (pintype "bidirectional"))
    )
    (net (code "4") (name "ADC_2") (class "Default")
      (node (ref "CON_ANALOG1") (pin "5") (pinfunction "5_5") (pintype "bidirectional"))
      (node (ref "LED5") (pin "C") (pinfunction "C_C") (pintype "passive"))
      (node (ref "U2") (pin "8") (pinfunction "PC0-ADC10_8") (pintype "bidirectional"))
    )
    (net (code "5") (name "ADC_3") (class "Default")
      (node (ref "CON_ANALOG1") (pin "6") (pinfunction "6_6") (pintype "bidirectional"))
      (node (ref "LED6") (pin "C") (pinfunction "C_C") (pintype "passive"))
      (node (ref "U2") (pin "9") (pinfunction "PC1-ADC11/ETH_(R)MII_MDC_9") (pintype "bidirectional"))
    )
    (net (code "6") (name "ADC_4") (class "Default")
      (node (ref "CON_ANALOG2") (pin "4") (pinfunction "4_4") (pintype "bidirectional"))
      (node (ref "LED7") (pin "C") (pinfunction "C_C") (pintype "passive"))
      (node (ref "U2") (pin "25") (pinfunction "PC5-ADC15ETH_(R)MII_RXD1_25") (pintype "bidirectional"))
    )
    (net (code "7") (name "ADC_6") (class "Default")
      (node (ref "CON_ANALOG2") (pin "5") (pinfunction "5_5") (pintype "bidirectional"))
      (node (ref "LED8") (pin "C") (pinfunction "C_C") (pintype "passive"))
      (node (ref "U2") (pin "10") (pinfunction "PC2-ADC12/ETH_MII_TXD2_10") (pintype "bidirectional"))
    )
    (net (code "8") (name "BARO_DRDY") (class "Default")
      (node (ref "U2") (pin "26") (pinfunction "PB0-ADC8/TIM3CH3/ETH_MII_RXD2-TIM1CH2N_26") (pintype "bidirectional"))
      (node (ref "U3") (pin "2") (pinfunction "EOC_2") (pintype "output"))
    )
    (net (code "9") (name "BOOT0") (class "Default")
      (node (ref "CON_ANALOG2") (pin "6") (pinfunction "6_6") (pintype "bidirectional"))
      (node (ref "R30") (pin "P$2") (pinfunction "2_P$2") (pintype "passive"))
      (node (ref "U2") (pin "60") (pinfunction "BOOT0_60") (pintype "input"))
    )
    (net (code "10") (name "CAN_H") (class "Default")
      (node (ref "JP21") (pin "5") (pinfunction "5_5") (pintype "passive"))
      (node (ref "R58") (pin "P$1") (pinfunction "1_P$1") (pintype "passive"))
      (node (ref "U1") (pin "7") (pinfunction "CANH_7") (pintype "bidirectional"))
    )
    (net (code "11") (name "CAN_L") (class "Default")
      (node (ref "JP21") (pin "4") (pinfunction "4_4") (pintype "passive"))
      (node (ref "R59") (pin "P$2") (pinfunction "2_P$2") (pintype "passive"))
      (node (ref "U1") (pin "6") (pinfunction "CANL_6") (pintype "bidirectional"))
    )
    (net (code "12") (name "CAN_RX") (class "Default")
      (node (ref "U1") (pin "4") (pinfunction "RXD_4") (pintype "output"))
      (node (ref "U2") (pin "61") (pinfunction "PB8-TIM4CH3/ETH_MII_TXD3-I2C1SCL/CAN1RX_61") (pintype "bidirectional"))
    )
    (net (code "13") (name "CAN_TX") (class "Default")
      (node (ref "U1") (pin "1") (pinfunction "TXD_1") (pintype "input"))
      (node (ref "U2") (pin "62") (pinfunction "PB9-TIM4CH4-I2C1SDA/CAN1TX_62") (pintype "bidirectional"))
    )
    (net (code "14") (name "EXTSPI_DRDY") (class "Default")
      (node (ref "JP22") (pin "7") (pinfunction "7_7") (pintype "passive"))
      (node (ref "U2") (pin "27") (pinfunction "PB1-ADC9/TIM3CH4/ETH_MII_RXD3-TIM1CH3N_27") (pintype "bidirectional"))
    )
    (net (code "15") (name "EXTSPI_MISO") (class "Default")
      (node (ref "JP22") (pin "4") (pinfunction "4_4") (pintype "passive"))
      (node (ref "U2") (pin "22") (pinfunction "PA6-SPI1MISO/ADC6/TIM3CH1-TIM1BKIN_22") (pintype "bidirectional"))
    )
    (net (code "16") (name "EXTSPI_MOSI") (class "Default")
      (node (ref "JP22") (pin "3") (pinfunction "3_3") (pintype "passive"))
      (node (ref "U2") (pin "23") (pinfunction "PA7-SPI1MOSI/ADC7/TIM3CH2/ETH_MII_RX_DV/ETH_RMII_CRS_DV-TIM1CH1N_23") (pintype "bidirectional"))
    )
    (net (code "17") (name "EXTSPI_SCK") (class "Default")
      (node (ref "JP22") (pin "5") (pinfunction "5_5") (pintype "passive"))
      (node (ref "U2") (pin "21") (pinfunction "PA5-SPI1SCK/DAC2/ADC5_21") (pintype "bidirectional"))
    )
    (net (code "18") (name "EXTSPI_SS") (class "Default")
      (node (ref "JP22") (pin "6") (pinfunction "6_6") (pintype "passive"))
      (node (ref "U2") (pin "20") (pinfunction "PA4-SPI1NSS/DAC1/USART2CK/ADC4-SPI3NSS/I2S3WS_20") (pintype "bidirectional"))
    )
    (net (code "19") (name "GND") (class "Default")
      (node (ref "C1") (pin "P$2") (pinfunction "2_P$2") (pintype "passive"))
      (node (ref "C10") (pin "P$1") (pinfunction "1_P$1") (pintype "passive"))
      (node (ref "C11") (pin "P$1") (pinfunction "1_P$1") (pintype "passive"))
      (node (ref "C12") (pin "P$1") (pinfunction "1_P$1") (pintype "passive"))
      (node (ref "C13") (pin "P$2") (pinfunction "2_P$2") (pintype "passive"))
      (node (ref "C14") (pin "P$1") (pinfunction "1_P$1") (pintype "passive"))
      (node (ref "C15") (pin "P$2") (pinfunction "2_P$2") (pintype "passive"))
      (node (ref "C2") (pin "P$2") (pinfunction "2_P$2") (pintype "passive"))
      (node (ref "C26") (pin "P$2") (pinfunction "2_P$2") (pintype "passive"))
      (node (ref "C27") (pin "P$1") (pinfunction "1_P$1") (pintype "passive"))
      (node (ref "C28") (pin "-") (pinfunction "-_-") (pintype "passive"))
      (node (ref "C3") (pin "P$2") (pinfunction "2_P$2") (pintype "passive"))
      (node (ref "C31") (pin "P$1") (pinfunction "1_P$1") (pintype "passive"))
      (node (ref "C35") (pin "P$2") (pinfunction "2_P$2") (pintype "passive"))
      (node (ref "C36") (pin "P$2") (pinfunction "2_P$2") (pintype "passive"))
      (node (ref "C37") (pin "-") (pinfunction "-_-") (pintype "passive"))
      (node (ref "C38") (pin "P$2") (pinfunction "2_P$2") (pintype "passive"))
      (node (ref "C39") (pin "-") (pinfunction "-_-") (pintype "passive"))
      (node (ref "C4") (pin "P$1") (pinfunction "1_P$1") (pintype "passive"))
      (node (ref "C42") (pin "P$1") (pinfunction "1_P$1") (pintype "passive"))
      (node (ref "C5") (pin "P$1") (pinfunction "1_P$1") (pintype "passive"))
      (node (ref "C6") (pin "P$2") (pinfunction "2_P$2") (pintype "passive"))
      (node (ref "C7") (pin "P$1") (pinfunction "1_P$1") (pintype "passive"))
      (node (ref "C8") (pin "P$1") (pinfunction "1_P$1") (pintype "passive"))
      (node (ref "C9") (pin "P$2") (pinfunction "2_P$2") (pintype "passive"))
      (node (ref "CON_ANALOG1") (pin "1") (pinfunction "1_1") (pintype "bidirectional"))
      (node (ref "CON_ANALOG2") (pin "1") (pinfunction "1_1") (pintype "bidirectional"))
      (node (ref "IC9") (pin "2") (pinfunction "GND_2") (pintype "bidirectional"))
      (node (ref "IMU") (pin "P$1") (pinfunction "GND1_P$1") (pintype "bidirectional"))
      (node (ref "IMU") (pin "P$14") (pinfunction "GND4_P$14") (pintype "bidirectional"))
      (node (ref "IMU") (pin "P$7") (pinfunction "GND2_P$7") (pintype "bidirectional"))
      (node (ref "J1") (pin "1") (pinfunction "1_1") (pintype "bidirectional"))
      (node (ref "J2") (pin "1") (pinfunction "1_1") (pintype "bidirectional"))
      (node (ref "J3") (pin "1") (pinfunction "1_1") (pintype "bidirectional"))
      (node (ref "J4") (pin "1") (pinfunction "1_1") (pintype "bidirectional"))
      (node (ref "J5") (pin "1") (pinfunction "1_1") (pintype "bidirectional"))
      (node (ref "J6") (pin "1") (pinfunction "1_1") (pintype "bidirectional"))
      (node (ref "J7") (pin "1") (pinfunction "1_1") (pintype "bidirectional"))
      (node (ref "J8") (pin "1") (pinfunction "1_1") (pintype "bidirectional"))
      (node (ref "JP12") (pin "P$2") (pinfunction "2_P$2") (pintype "passive"))
      (node (ref "JP13") (pin "P$2") (pinfunction "2_P$2") (pintype "passive"))
      (node (ref "JP14") (pin "1") (pinfunction "1_1") (pintype "passive"))
      (node (ref "JP15") (pin "1") (pinfunction "1_1") (pintype "passive"))
      (node (ref "JP16") (pin "1") (pinfunction "1_1") (pintype "passive"))
      (node (ref "JP17") (pin "1") (pinfunction "1_1") (pintype "passive"))
      (node (ref "JP20") (pin "1") (pinfunction "1_1") (pintype "passive"))
      (node (ref "JP20") (pin "4") (pinfunction "4_4") (pintype "passive"))
      (node (ref "JP21") (pin "1") (pinfunction "1_1") (pintype "passive"))
      (node (ref "JP22") (pin "1") (pinfunction "1_1") (pintype "passive"))
      (node (ref "JP23") (pin "4") (pinfunction "4_4") (pintype "passive"))
      (node (ref "JTAG") (pin "3") (pinfunction "3_3") (pintype "bidirectional"))
      (node (ref "JTAG") (pin "5") (pinfunction "5_5") (pintype "bidirectional"))
      (node (ref "JTAG") (pin "7") (pinfunction "7_7") (pintype "bidirectional"))
      (node (ref "JTAG") (pin "9") (pinfunction "9_9") (pintype "bidirectional"))
      (node (ref "LED4") (pin "C") (pinfunction "C_C") (pintype "passive"))
      (node (ref "LT_I2C2") (pin "1") (pinfunction "GND_1") (pintype "bidirectional"))
      (node (ref "Q1") (pin "P$2") (pinfunction "P$2_P$2") (pintype "bidirectional"))
      (node (ref "Q1") (pin "P$4") (pinfunction "P$4_P$4") (pintype "bidirectional"))
      (node (ref "R18") (pin "P$2") (pinfunction "2_P$2") (pintype "passive"))
      (node (ref "R30") (pin "P$1") (pinfunction "1_P$1") (pintype "passive"))
      (node (ref "R55") (pin "P$1") (pinfunction "1_P$1") (pintype "passive"))
      (node (ref "R61") (pin "P$2") (pinfunction "2_P$2") (pintype "passive"))
      (node (ref "U1") (pin "2") (pinfunction "VSS_2") (pintype "power_in"))
      (node (ref "U2") (pin "12") (pinfunction "VSSA_12") (pintype "power_in"))
      (node (ref "U2") (pin "18") (pinfunction "VSS4_18") (pintype "bidirectional"))
      (node (ref "U2") (pin "63") (pinfunction "VSS3_63") (pintype "power_in"))
      (node (ref "U3") (pin "1") (pinfunction "GND_1") (pintype "power_in"))
      (node (ref "VREG1") (pin "5") (pinfunction "GND4_5") (pintype "bidirectional"))
      (node (ref "VREG1") (pin "6") (pinfunction "GND3_6") (pintype "bidirectional"))
      (node (ref "VREG1") (pin "7") (pinfunction "GND2_7") (pintype "bidirectional"))
      (node (ref "VREG1") (pin "8") (pinfunction "GND1_8") (pintype "bidirectional"))
    )
    (net (code "20") (name "I2C2_SCL") (class "Default")
      (node (ref "IMU") (pin "P$10") (pinfunction "SCL_P$10") (pintype "bidirectional"))
      (node (ref "JP14") (pin "3") (pinfunction "3_3") (pintype "passive"))
      (node (ref "R4") (pin "P$2") (pinfunction "2_P$2") (pintype "passive"))
      (node (ref "U2") (pin "29") (pinfunction "PB10-I2C2SCL/USART3TX/ETH_MII_RX_ER-TIM2CH3_29") (pintype "bidirectional"))
      (node (ref "U3") (pin "6") (pinfunction "SCL_6") (pintype "input"))
    )
    (net (code "21") (name "I2C2_SDA") (class "Default")
      (node (ref "IMU") (pin "P$11") (pinfunction "SDA_P$11") (pintype "bidirectional"))
      (node (ref "JP14") (pin "4") (pinfunction "4_4") (pintype "passive"))
      (node (ref "R5") (pin "P$2") (pinfunction "2_P$2") (pintype "passive"))
      (node (ref "U2") (pin "30") (pinfunction "PB11-I2C2SDA/USART3RX/ETH_(R)MII_TX_EN-TIM2CH4_30") (pintype "bidirectional"))
      (node (ref "U3") (pin "7") (pinfunction "SDA_7") (pintype "bidirectional"))
    )
    (net (code "22") (name "IMU_ACC_CS") (class "Default")
      (node (ref "IMU") (pin "P$12") (pinfunction "ACC_CS_P$12") (pintype "bidirectional"))
      (node (ref "U2") (pin "33") (pinfunction "PB12-SPI2NSS/I2S2WS/I2C2SMBA/USART3CK/TIM1BKIN/CAN2RX/ETH_(R)MII_TXD0_33") (pintype "bidirectional"))
    )
    (net (code "23") (name "IMU_ACC_DRDY") (class "Default")
      (node (ref "IMU") (pin "P$13") (pinfunction "ACC_DRDY_P$13") (pintype "bidirectional"))
      (node (ref "U2") (pin "28") (pinfunction "PB2/BOOT1_28") (pintype "bidirectional"))
    )
    (net (code "24") (name "IMU_GYRO_DRDY") (class "Default")
      (node (ref "IMU") (pin "P$9") (pinfunction "GYRO_DRDY_P$9") (pintype "bidirectional"))
      (node (ref "U2") (pin "3") (pinfunction "PC14-OSC32_IN_3") (pintype "bidirectional"))
    )
    (net (code "25") (name "IMU_GYRO_SS") (class "Default")
      (node (ref "IMU") (pin "P$8") (pinfunction "GND3_P$8") (pintype "bidirectional"))
      (node (ref "U2") (pin "2") (pinfunction "PC13-TAMPER-RTC_2") (pintype "bidirectional"))
    )
    (net (code "26") (name "IMU_MAG_DRDY") (class "Default")
      (node (ref "IMU") (pin "P$6") (pinfunction "MAG_DRDY_P$6") (pintype "bidirectional"))
      (node (ref "R29") (pin "P$2") (pinfunction "2_P$2") (pintype "passive"))
      (node (ref "U2") (pin "57") (pinfunction "PB5-I2C1SMBA/SPI3MOSI/ETH_(R)MII_PPS_OUT/I2S3SD-TIM3CH2/SPI1MOSI/CAN2RX_57") (pintype "bidirectional"))
    )
    (net (code "27") (name "IMU_SPI_MISO") (class "Default")
      (node (ref "IMU") (pin "P$3") (pinfunction "MISO_P$3") (pintype "bidirectional"))
      (node (ref "U2") (pin "35") (pinfunction "PB14-SPI2MISO/USART3RTS/TIM1CH2N_35") (pintype "bidirectional"))
    )
    (net (code "28") (name "IMU_SPI_MOSI") (class "Default")
      (node (ref "IMU") (pin "P$4") (pinfunction "MOSI_P$4") (pintype "bidirectional"))
      (node (ref "U2") (pin "36") (pinfunction "PB15-SPI2MOSI/I2S2SD/TIM1CH3N_36") (pintype "bidirectional"))
    )
    (net (code "29") (name "IMU_SPI_SCK") (class "Default")
      (node (ref "IMU") (pin "P$5") (pinfunction "SCK_P$5") (pintype "bidirectional"))
      (node (ref "U2") (pin "34") (pinfunction "PB13-SPI2SCK/I2S2CK/USART3CTS/TIM1CH1N/CAN2TX/ETH_(R)MII_TXD1_34") (pintype "bidirectional"))
    )
    (net (code "30") (name "JTAG_RST") (class "Default")
      (node (ref "C27") (pin "P$2") (pinfunction "2_P$2") (pintype "passive"))
      (node (ref "JTAG") (pin "10") (pinfunction "10_10") (pintype "bidirectional"))
      (node (ref "R7") (pin "P$1") (pinfunction "1_P$1") (pintype "passive"))
      (node (ref "U2") (pin "7") (pinfunction "NRST_7") (pintype "bidirectional"))
    )
    (net (code "31") (name "JTAG_TCK") (class "Default")
      (node (ref "JTAG") (pin "4") (pinfunction "4_4") (pintype "bidirectional"))
      (node (ref "U2") (pin "49") (pinfunction "PA14/JTCK/SWCLK_49") (pintype "bidirectional"))
    )
    (net (code "32") (name "JTAG_TDI") (class "Default")
      (node (ref "JTAG") (pin "8") (pinfunction "8_8") (pintype "bidirectional"))
      (node (ref "U2") (pin "50") (pinfunction "PA15/JTDI-SPI3NSS/I2S3WS-TIM2CH1ETR/SPI1NSS_50") (pintype "bidirectional"))
    )
    (net (code "33") (name "JTAG_TDO") (class "Default")
      (node (ref "JTAG") (pin "6") (pinfunction "6_6") (pintype "bidirectional"))
      (node (ref "U2") (pin "55") (pinfunction "PB3/JTDO-SPI3SCK/I2S3CK-TIM2CH2/TRACESWO/SPI1SCK_55") (pintype "bidirectional"))
    )
    (net (code "34") (name "JTAG_TMS") (class "Default")
      (node (ref "JTAG") (pin "2") (pinfunction "2_2") (pintype "bidirectional"))
      (node (ref "U2") (pin "46") (pinfunction "PA13/JTMS/SWDIO_46") (pintype "bidirectional"))
    )
    (net (code "35") (name "JTAG_TRST") (class "Default")
      (node (ref "JP15") (pin "4") (pinfunction "4_4") (pintype "passive"))
      (node (ref "LED1") (pin "C") (pinfunction "C_C") (pintype "passive"))
      (node (ref "U2") (pin "56") (pinfunction "PB4/JNTRST-SPI3MISO-TIM3CH1/SPI1MISO_56") (pintype "bidirectional"))
    )
    (net (code "36") (name "LED1") (class "Default")
      (node (ref "LED2") (pin "C") (pinfunction "C_C") (pintype "passive"))
      (node (ref "U2") (pin "41") (pinfunction "PA8-USART1CK/OTG_FS_SOF/MCO/TIM1CH1_41") (pintype "bidirectional"))
    )
    (net (code "37") (name "LED2") (class "Default")
      (node (ref "LED9") (pin "C") (pinfunction "C_C") (pintype "passive"))
      (node (ref "U2") (pin "4") (pinfunction "PC15-OSC32_OUT_4") (pintype "bidirectional"))
    )
    (net (code "38") (name "LT_I2C1_SCL") (class "Default")
      (node (ref "JP10") (pin "P$2") (pinfunction "2_P$2") (pintype "passive"))
      (node (ref "JP21") (pin "6") (pinfunction "6_6") (pintype "passive"))
      (node (ref "LT_I2C2") (pin "6") (pinfunction "SCL2_6") (pintype "bidirectional"))
      (node (ref "R44") (pin "P$1") (pinfunction "1_P$1") (pintype "passive"))
    )
    (net (code "39") (name "LT_I2C1_SDA") (class "Default")
      (node (ref "JP11") (pin "P$2") (pinfunction "2_P$2") (pintype "passive"))
      (node (ref "JP21") (pin "7") (pinfunction "7_7") (pintype "passive"))
      (node (ref "LT_I2C2") (pin "5") (pinfunction "SDA2_5") (pintype "bidirectional"))
      (node (ref "R43") (pin "P$1") (pinfunction "1_P$1") (pintype "passive"))
    )
    (net (code "40") (name "Net-(C13-1)") (class "Default")
      (node (ref "C13") (pin "P$1") (pinfunction "1_P$1") (pintype "passive"))
      (node (ref "IC9") (pin "4") (pinfunction "BYPASS_4") (pintype "bidirectional"))
    )
    (net (code "41") (name "Net-(C15-1)") (class "Default")
      (node (ref "C15") (pin "P$1") (pinfunction "1_P$1") (pintype "passive"))
      (node (ref "LT_I2C2") (pin "7") (pinfunction "VREF2_7") (pintype "bidirectional"))
      (node (ref "LT_I2C2") (pin "8") (pinfunction "EN_8") (pintype "bidirectional"))
      (node (ref "R25") (pin "P$1") (pinfunction "1_P$1") (pintype "passive"))
    )
    (net (code "42") (name "Net-(C31-2)") (class "Default")
      (node (ref "C28") (pin "+") (pinfunction "+_+") (pintype "passive"))
      (node (ref "C31") (pin "P$2") (pinfunction "2_P$2") (pintype "passive"))
      (node (ref "L1") (pin "P$2") (pinfunction "2_P$2") (pintype "passive"))
      (node (ref "U2") (pin "13") (pinfunction "VDDA_13") (pintype "power_in"))
    )
    (net (code "43") (name "Net-(C35-1)") (class "Default")
      (node (ref "C35") (pin "P$1") (pinfunction "1_P$1") (pintype "passive"))
      (node (ref "VREG1") (pin "4") (pinfunction "BYP_4") (pintype "bidirectional"))
    )
    (net (code "44") (name "Net-(C42-2)") (class "Default")
      (node (ref "C42") (pin "P$2") (pinfunction "2_P$2") (pintype "passive"))
      (node (ref "R58") (pin "P$2") (pinfunction "2_P$2") (pintype "passive"))
      (node (ref "R59") (pin "P$1") (pinfunction "1_P$1") (pintype "passive"))
      (node (ref "R60") (pin "P$2") (pinfunction "2_P$2") (pintype "passive"))
      (node (ref "R61") (pin "P$1") (pinfunction "1_P$1") (pintype "passive"))
    )
    (net (code "45") (name "Net-(R1-1)") (class "Default")
      (node (ref "JP23") (pin "2") (pinfunction "2_2") (pintype "passive"))
      (node (ref "R1") (pin "P$1") (pinfunction "1_P$1") (pintype "passive"))
    )
    (net (code "46") (name "Net-(R2-1)") (class "Default")
      (node (ref "JP23") (pin "3") (pinfunction "3_3") (pintype "passive"))
      (node (ref "R2") (pin "P$1") (pinfunction "1_P$1") (pintype "passive"))
    )
    (net (code "47") (name "Net-(R8-1)") (class "Default")
      (node (ref "LED1") (pin "A") (pinfunction "A_A") (pintype "passive"))
      (node (ref "R8") (pin "P$1") (pinfunction "1_P$1") (pintype "passive"))
    )
    (net (code "48") (name "Net-(R9-1)") (class "Default")
      (node (ref "J1") (pin "2") (pinfunction "2_2") (pintype "bidirectional"))
      (node (ref "R9") (pin "P$1") (pinfunction "1_P$1") (pintype "passive"))
    )
    (net (code "49") (name "Net-(R10-1)") (class "Default")
      (node (ref "LED2") (pin "A") (pinfunction "A_A") (pintype "passive"))
      (node (ref "R10") (pin "P$1") (pinfunction "1_P$1") (pintype "passive"))
    )
    (net (code "50") (name "Net-(R11-1)") (class "Default")
      (node (ref "J2") (pin "2") (pinfunction "2_2") (pintype "bidirectional"))
      (node (ref "R11") (pin "P$1") (pinfunction "1_P$1") (pintype "passive"))
    )
    (net (code "51") (name "Net-(R12-1)") (class "Default")
      (node (ref "LED9") (pin "A") (pinfunction "A_A") (pintype "passive"))
      (node (ref "R12") (pin "P$1") (pinfunction "1_P$1") (pintype "passive"))
    )
    (net (code "52") (name "Net-(R13-1)") (class "Default")
      (node (ref "J4") (pin "2") (pinfunction "2_2") (pintype "bidirectional"))
      (node (ref "R13") (pin "P$1") (pinfunction "1_P$1") (pintype "passive"))
    )
    (net (code "53") (name "Net-(R14-1)") (class "Default")
      (node (ref "J5") (pin "2") (pinfunction "2_2") (pintype "bidirectional"))
      (node (ref "R14") (pin "P$1") (pinfunction "1_P$1") (pintype "passive"))
    )
    (net (code "54") (name "Net-(R15-1)") (class "Default")
      (node (ref "J6") (pin "2") (pinfunction "2_2") (pintype "bidirectional"))
      (node (ref "R15") (pin "P$1") (pinfunction "1_P$1") (pintype "passive"))
    )
    (net (code "55") (name "Net-(R16-1)") (class "Default")
      (node (ref "J7") (pin "2") (pinfunction "2_2") (pintype "bidirectional"))
      (node (ref "R16") (pin "P$1") (pinfunction "1_P$1") (pintype "passive"))
    )
    (net (code "56") (name "Net-(R19-1)") (class "Default")
      (node (ref "J8") (pin "2") (pinfunction "2_2") (pintype "bidirectional"))
      (node (ref "R19") (pin "P$1") (pinfunction "1_P$1") (pintype "passive"))
    )
    (net (code "57") (name "Net-(R20-1)") (class "Default")
      (node (ref "J3") (pin "2") (pinfunction "2_2") (pintype "bidirectional"))
      (node (ref "R20") (pin "P$1") (pinfunction "1_P$1") (pintype "passive"))
    )
    (net (code "58") (name "Net-(R23-1)") (class "Default")
      (node (ref "LED4") (pin "A") (pinfunction "A_A") (pintype "passive"))
      (node (ref "R23") (pin "P$1") (pinfunction "1_P$1") (pintype "passive"))
    )
    (net (code "59") (name "Net-(R32-1)") (class "Default")
      (node (ref "LED3") (pin "A") (pinfunction "A_A") (pintype "passive"))
      (node (ref "R32") (pin "P$1") (pinfunction "1_P$1") (pintype "passive"))
    )
    (net (code "60") (name "Net-(R35-1)") (class "Default")
      (node (ref "LED5") (pin "A") (pinfunction "A_A") (pintype "passive"))
      (node (ref "R35") (pin "P$1") (pinfunction "1_P$1") (pintype "passive"))
    )
    (net (code "61") (name "Net-(R36-1)") (class "Default")
      (node (ref "LED6") (pin "A") (pinfunction "A_A") (pintype "passive"))
      (node (ref "R36") (pin "P$1") (pinfunction "1_P$1") (pintype "passive"))
    )
    (net (code "62") (name "Net-(R37-1)") (class "Default")
      (node (ref "LED7") (pin "A") (pinfunction "A_A") (pintype "passive"))
      (node (ref "R37") (pin "P$1") (pinfunction "1_P$1") (pintype "passive"))
    )
    (net (code "63") (name "Net-(R38-1)") (class "Default")
      (node (ref "LED8") (pin "A") (pinfunction "A_A") (pintype "passive"))
      (node (ref "R38") (pin "P$1") (pinfunction "1_P$1") (pintype "passive"))
    )
    (net (code "64") (name "Net-(R55-2)") (class "Default")
      (node (ref "R55") (pin "P$2") (pinfunction "2_P$2") (pintype "passive"))
      (node (ref "R56") (pin "P$1") (pinfunction "1_P$1") (pintype "passive"))
      (node (ref "U1") (pin "8") (pinfunction "RS_8") (pintype "input"))
    )
    (net (code "65") (name "OSC_IN") (class "Default")
      (node (ref "C4") (pin "P$2") (pinfunction "2_P$2") (pintype "passive"))
      (node (ref "Q1") (pin "P$3") (pinfunction "P$3_P$3") (pintype "bidirectional"))
      (node (ref "U2") (pin "5") (pinfunction "PD0-OSC_IN-CAN1RX_5") (pintype "input"))
    )
    (net (code "66") (name "OSC_OUT") (class "Default")
      (node (ref "C6") (pin "P$1") (pinfunction "1_P$1") (pintype "passive"))
      (node (ref "Q1") (pin "P$1") (pinfunction "P$1_P$1") (pintype "bidirectional"))
      (node (ref "U2") (pin "6") (pinfunction "PD1-OSC_OUT-CAN1TX_6") (pintype "output"))
    )
    (net (code "67") (name "PC12") (class "Default")
      (node (ref "JP15") (pin "3") (pinfunction "3_3") (pintype "passive"))
      (node (ref "U2") (pin "53") (pinfunction "PC12-USART5TX-USART3CK/SPI3MOSI/I2S3SD_53") (pintype "bidirectional"))
    )
    (net (code "68") (name "S1") (class "Default")
      (node (ref "J1") (pin "3") (pinfunction "3_3") (pintype "bidirectional"))
      (node (ref "R41") (pin "P$1") (pinfunction "1_P$1") (pintype "passive"))
    )
    (net (code "69") (name "S2") (class "Default")
      (node (ref "J2") (pin "3") (pinfunction "3_3") (pintype "bidirectional"))
      (node (ref "R42") (pin "P$1") (pinfunction "1_P$1") (pintype "passive"))
    )
    (net (code "70") (name "S3") (class "Default")
      (node (ref "J3") (pin "3") (pinfunction "3_3") (pintype "bidirectional"))
      (node (ref "R45") (pin "P$1") (pinfunction "1_P$1") (pintype "passive"))
    )
    (net (code "71") (name "S4") (class "Default")
      (node (ref "J4") (pin "3") (pinfunction "3_3") (pintype "bidirectional"))
      (node (ref "R27") (pin "P$1") (pinfunction "1_P$1") (pintype "passive"))
    )
    (net (code "72") (name "S5") (class "Default")
      (node (ref "J5") (pin "3") (pinfunction "3_3") (pintype "bidirectional"))
      (node (ref "R28") (pin "P$1") (pinfunction "1_P$1") (pintype "passive"))
    )
    (net (code "73") (name "S6") (class "Default")
      (node (ref "J6") (pin "3") (pinfunction "3_3") (pintype "bidirectional"))
      (node (ref "R31") (pin "P$1") (pinfunction "1_P$1") (pintype "passive"))
    )
    (net (code "74") (name "S7") (class "Default")
      (node (ref "J7") (pin "3") (pinfunction "3_3") (pintype "bidirectional"))
      (node (ref "R39") (pin "P$1") (pinfunction "1_P$1") (pintype "passive"))
    )
    (net (code "75") (name "S8") (class "Default")
      (node (ref "J8") (pin "3") (pinfunction "3_3") (pintype "bidirectional"))
      (node (ref "R40") (pin "P$1") (pinfunction "1_P$1") (pintype "passive"))
    )
    (net (code "76") (name "SERVO_1") (class "Default")
      (node (ref "R41") (pin "P$2") (pinfunction "2_P$2") (pintype "passive"))
      (node (ref "U2") (pin "37") (pinfunction "PC6-I2S2MCK-TIM3CH1_37") (pintype "bidirectional"))
    )
    (net (code "77") (name "SERVO_2") (class "Default")
      (node (ref "R42") (pin "P$2") (pinfunction "2_P$2") (pintype "passive"))
      (node (ref "U2") (pin "38") (pinfunction "PC7-I2S3MCK-TIM3CH2_38") (pintype "bidirectional"))
    )
    (net (code "78") (name "SERVO_3") (class "Default")
      (node (ref "R45") (pin "P$2") (pinfunction "2_P$2") (pintype "passive"))
      (node (ref "U2") (pin "39") (pinfunction "PC8-TIM3CH3_39") (pintype "bidirectional"))
    )
    (net (code "79") (name "SERVO_4") (class "Default")
      (node (ref "R27") (pin "P$2") (pinfunction "2_P$2") (pintype "passive"))
      (node (ref "U2") (pin "40") (pinfunction "PC9-TIM3CH4_40") (pintype "bidirectional"))
    )
    (net (code "80") (name "SERVO_5") (class "Default")
      (node (ref "R28") (pin "P$2") (pinfunction "2_P$2") (pintype "passive"))
      (node (ref "U2") (pin "14") (pinfunction "PA0-WKUP/USART2CTS/ADC0/TIM2CH1ETR/TIM5CH1/ETH_MII_CRS_WKUP_14") (pintype "bidirectional"))
    )
    (net (code "81") (name "SERVO_6") (class "Default")
      (node (ref "R31") (pin "P$2") (pinfunction "2_P$2") (pintype "passive"))
      (node (ref "U2") (pin "15") (pinfunction "PA1-USART2RTS/ADC1/TIM5CH2/TIM2CH2/ETH_MII_RX_CLK/ETH_RMII_REF_CLK_15") (pintype "bidirectional"))
    )
    (net (code "82") (name "SERVO_7{slash}I2C1_SCL") (class "Default")
      (node (ref "JP10") (pin "P$1") (pinfunction "1_P$1") (pintype "passive"))
      (node (ref "LT_I2C2") (pin "3") (pinfunction "SCL1_3") (pintype "bidirectional"))
      (node (ref "R33") (pin "P$1") (pinfunction "1_P$1") (pintype "passive"))
      (node (ref "R39") (pin "P$2") (pinfunction "2_P$2") (pintype "passive"))
      (node (ref "U2") (pin "58") (pinfunction "PB6-I2C1SCL/TIM4CH1-USART1TX/CAN2TX_58") (pintype "bidirectional"))
    )
    (net (code "83") (name "SERVO_8{slash}I2C1_SDA") (class "Default")
      (node (ref "JP11") (pin "P$1") (pinfunction "1_P$1") (pintype "passive"))
      (node (ref "LT_I2C2") (pin "4") (pinfunction "SDA1_4") (pintype "bidirectional"))
      (node (ref "R34") (pin "P$1") (pinfunction "1_P$1") (pintype "passive"))
      (node (ref "R40") (pin "P$2") (pinfunction "2_P$2") (pintype "passive"))
      (node (ref "U2") (pin "59") (pinfunction "PB7-I2C1SDA/TIM4CH2-USART1RX_59") (pintype "bidirectional"))
    )
    (net (code "84") (name "SERVO_BUS") (class "Default")
      (node (ref "JP1") (pin "P$1") (pinfunction "1_P$1") (pintype "passive"))
      (node (ref "R11") (pin "P$2") (pinfunction "2_P$2") (pintype "passive"))
      (node (ref "R13") (pin "P$2") (pinfunction "2_P$2") (pintype "passive"))
      (node (ref "R14") (pin "P$2") (pinfunction "2_P$2") (pintype "passive"))
      (node (ref "R15") (pin "P$2") (pinfunction "2_P$2") (pintype "passive"))
      (node (ref "R16") (pin "P$2") (pinfunction "2_P$2") (pintype "passive"))
      (node (ref "R19") (pin "P$2") (pinfunction "2_P$2") (pintype "passive"))
      (node (ref "R20") (pin "P$2") (pinfunction "2_P$2") (pintype "passive"))
      (node (ref "R9") (pin "P$2") (pinfunction "2_P$2") (pintype "passive"))
    )
    (net (code "85") (name "U1_U5_POW") (class "Default")
      (node (ref "JP20") (pin "2") (pinfunction "2_2") (pintype "passive"))
      (node (ref "JP20") (pin "5") (pinfunction "5_5") (pintype "passive"))
      (node (ref "JP8") (pin "P$2") (pinfunction "2_P$2") (pintype "passive"))
      (node (ref "JP9") (pin "P$2") (pinfunction "2_P$2") (pintype "passive"))
      (node (ref "R24") (pin "P$1") (pinfunction "1_P$1") (pintype "passive"))
      (node (ref "R6") (pin "P$1") (pinfunction "1_P$1") (pintype "passive"))
    )
    (net (code "86") (name "U2_POW") (class "Default")
      (node (ref "JP16") (pin "2") (pinfunction "2_2") (pintype "passive"))
      (node (ref "JP4") (pin "P$2") (pinfunction "2_P$2") (pintype "passive"))
      (node (ref "JP5") (pin "P$2") (pinfunction "2_P$2") (pintype "passive"))
      (node (ref "R26") (pin "P$1") (pinfunction "1_P$1") (pintype "passive"))
    )
    (net (code "87") (name "U3_POW") (class "Default")
      (node (ref "JP17") (pin "2") (pinfunction "2_2") (pintype "passive"))
      (node (ref "JP6") (pin "P$2") (pinfunction "2_P$2") (pintype "passive"))
      (node (ref "JP7") (pin "P$2") (pinfunction "2_P$2") (pintype "passive"))
      (node (ref "R3") (pin "P$1") (pinfunction "1_P$1") (pintype "passive"))
    )
    (net (code "88") (name "UART1_RX") (class "Default")
      (node (ref "JP20") (pin "3") (pinfunction "3_3") (pintype "passive"))
      (node (ref "R24") (pin "P$2") (pinfunction "2_P$2") (pintype "passive"))
      (node (ref "U2") (pin "43") (pinfunction "PA10-USART1RX/TIM1CH3/OTG_FS_ID_43") (pintype "bidirectional"))
    )
    (net (code "89") (name "UART2_RX") (class "Default")
      (node (ref "JP16") (pin "4") (pinfunction "4_4") (pintype "passive"))
      (node (ref "R26") (pin "P$2") (pinfunction "2_P$2") (pintype "passive"))
      (node (ref "U2") (pin "17") (pinfunction "PA3-USART2RX/TIM5CH4/ADC3/TIM2CH4/ETH_MII_COL_17") (pintype "bidirectional"))
    )
    (net (code "90") (name "UART2_TX") (class "Default")
      (node (ref "JP16") (pin "3") (pinfunction "3_3") (pintype "passive"))
      (node (ref "U2") (pin "16") (pinfunction "PA2-USART2TX/TIM5CH3/ADC2/TIM2CH3/ETH_(R)MII_MDIO_16") (pintype "bidirectional"))
    )
    (net (code "91") (name "UART3_RX") (class "Default")
      (node (ref "JP17") (pin "4") (pinfunction "4_4") (pintype "passive"))
      (node (ref "R3") (pin "P$2") (pinfunction "2_P$2") (pintype "passive"))
      (node (ref "U2") (pin "52") (pinfunction "PC11-USART4RX-USART3RX/SPI3MISO_52") (pintype "bidirectional"))
    )
    (net (code "92") (name "UART3_TX") (class "Default")
      (node (ref "JP17") (pin "3") (pinfunction "3_3") (pintype "passive"))
      (node (ref "U2") (pin "51") (pinfunction "PC10-USART4TX-USART3TX/SPI3SCK/I2S3CK_51") (pintype "bidirectional"))
    )
    (net (code "93") (name "UART5_RX") (class "Default")
      (node (ref "JP20") (pin "6") (pinfunction "6_6") (pintype "passive"))
      (node (ref "R6") (pin "P$2") (pinfunction "2_P$2") (pintype "passive"))
      (node (ref "U2") (pin "54") (pinfunction "PD2-TIM3ETR/USART5RX_54") (pintype "bidirectional"))
    )
    (net (code "94") (name "USB_DM") (class "Default")
      (node (ref "R1") (pin "P$2") (pinfunction "2_P$2") (pintype "passive"))
      (node (ref "U2") (pin "44") (pinfunction "PA11-USART1CTS/CAN1RX/OTG_FS_DM/TIM1CH4_44") (pintype "bidirectional"))
    )
    (net (code "95") (name "USB_DP") (class "Default")
      (node (ref "R2") (pin "P$2") (pinfunction "2_P$2") (pintype "passive"))
      (node (ref "U2") (pin "45") (pinfunction "PA12-USART1RTS/CAN1TX/OTG_FS_DP/TIM1ETR_45") (pintype "bidirectional"))
    )
    (net (code "96") (name "USB_VBUS") (class "Default")
      (node (ref "D3") (pin "A") (pinfunction "A_A") (pintype "passive"))
      (node (ref "JP23") (pin "1") (pinfunction "1_1") (pintype "passive"))
      (node (ref "U2") (pin "42") (pinfunction "PA9-USART1TX/TIM1CH2/OTG_FS_VBUS_42") (pintype "bidirectional"))
    )
    (net (code "97") (name "VREF") (class "Default")
      (node (ref "U1") (pin "5") (pinfunction "VREF_5") (pintype "power_in"))
    )
    (net (code "98") (name "VSS1") (class "Default")
      (node (ref "C7") (pin "P$2") (pinfunction "2_P$2") (pintype "passive"))
      (node (ref "JP12") (pin "P$1") (pinfunction "1_P$1") (pintype "passive"))
      (node (ref "U2") (pin "31") (pinfunction "VSS1_31") (pintype "power_in"))
    )
    (net (code "99") (name "VSS2") (class "Default")
      (node (ref "C14") (pin "P$2") (pinfunction "2_P$2") (pintype "passive"))
      (node (ref "JP13") (pin "P$1") (pinfunction "1_P$1") (pintype "passive"))
      (node (ref "U2") (pin "47") (pinfunction "VSS2_47") (pintype "power_in"))
    )
    (net (code "100") (name "V_BAT") (class "Default")
      (node (ref "JP2") (pin "P$2") (pinfunction "2_P$2") (pintype "passive"))
      (node (ref "JP21") (pin "2") (pinfunction "2_2") (pintype "passive"))
      (node (ref "R17") (pin "P$1") (pinfunction "1_P$1") (pintype "passive"))
    )
    (net (code "101") (name "V_BAT_MEAS") (class "Default")
      (node (ref "R17") (pin "P$2") (pinfunction "2_P$2") (pintype "passive"))
      (node (ref "R18") (pin "P$1") (pinfunction "1_P$1") (pintype "passive"))
      (node (ref "U2") (pin "24") (pinfunction "PC4-ADC14/ETH_(R)MII_RXD0_24") (pintype "bidirectional"))
    )
    (net (code "102") (name "V_IN") (class "Default")
      (node (ref "C3") (pin "P$1") (pinfunction "1_P$1") (pintype "passive"))
      (node (ref "C38") (pin "P$1") (pinfunction "1_P$1") (pintype "passive"))
      (node (ref "C39") (pin "+") (pinfunction "+_+") (pintype "passive"))
      (node (ref "D3") (pin "C") (pinfunction "C_C") (pintype "passive"))
      (node (ref "IC9") (pin "1") (pinfunction "VIN_1") (pintype "bidirectional"))
      (node (ref "IC9") (pin "3") (pinfunction "ON/OFF_3") (pintype "bidirectional"))
      (node (ref "IMU") (pin "P$2") (pinfunction "VCC_P$2") (pintype "bidirectional"))
      (node (ref "JP1") (pin "P$2") (pinfunction "2_P$2") (pintype "passive"))
      (node (ref "JP2") (pin "P$1") (pinfunction "1_P$1") (pintype "passive"))
      (node (ref "JP21") (pin "3") (pinfunction "3_3") (pintype "passive"))
      (node (ref "JP3") (pin "P$1") (pinfunction "1_P$1") (pintype "passive"))
      (node (ref "JP4") (pin "P$1") (pinfunction "1_P$1") (pintype "passive"))
      (node (ref "JP6") (pin "P$1") (pinfunction "1_P$1") (pintype "passive"))
      (node (ref "JP8") (pin "P$1") (pinfunction "1_P$1") (pintype "passive"))
      (node (ref "R23") (pin "P$2") (pinfunction "2_P$2") (pintype "passive"))
      (node (ref "VREG1") (pin "1") (pinfunction "ENABLE_1") (pintype "bidirectional"))
      (node (ref "VREG1") (pin "2") (pinfunction "VIN_2") (pintype "bidirectional"))
    )
    (net (code "103") (name "unconnected-(CON_USB_MICRO-1-PadPIN_1)") (class "Default")
      (node (ref "CON_USB_MICRO") (pin "PIN_1") (pinfunction "1_PIN_1") (pintype "input"))
    )
    (net (code "104") (name "unconnected-(CON_USB_MICRO-2-PadPIN_2)") (class "Default")
      (node (ref "CON_USB_MICRO") (pin "PIN_2") (pinfunction "2_PIN_2") (pintype "input"))
    )
    (net (code "105") (name "unconnected-(CON_USB_MICRO-3-PadPIN_3)") (class "Default")
      (node (ref "CON_USB_MICRO") (pin "PIN_3") (pinfunction "3_PIN_3") (pintype "input"))
    )
    (net (code "106") (name "unconnected-(CON_USB_MICRO-4-PadPIN_4)") (class "Default")
      (node (ref "CON_USB_MICRO") (pin "PIN_4") (pinfunction "4_PIN_4") (pintype "input"))
    )
    (net (code "107") (name "unconnected-(CON_USB_MICRO-5-PadPIN_5)") (class "Default")
      (node (ref "CON_USB_MICRO") (pin "PIN_5") (pinfunction "5_PIN_5") (pintype "input"))
    )
    (net (code "108") (name "unconnected-(CON_USB_MICRO-S1-PadGND_LEFT)") (class "Default")
      (node (ref "CON_USB_MICRO") (pin "GND_LEFT") (pinfunction "S1_GND_LEFT") (pintype "passive"))
    )
    (net (code "109") (name "unconnected-(CON_USB_MICRO-S2-PadGND_RIGHT)") (class "Default")
      (node (ref "CON_USB_MICRO") (pin "GND_RIGHT") (pinfunction "S2_GND_RIGHT") (pintype "passive"))
    )
    (net (code "110") (name "unconnected-(CON_USB_MICRO-S3-PadGND_UP_LEFT)") (class "Default")
      (node (ref "CON_USB_MICRO") (pin "GND_UP_LEFT") (pinfunction "S3_GND_UP_LEFT") (pintype "passive"))
    )
    (net (code "111") (name "unconnected-(CON_USB_MICRO-S4-PadGND_UP_RIGHT)") (class "Default")
      (node (ref "CON_USB_MICRO") (pin "GND_UP_RIGHT") (pinfunction "S4_GND_UP_RIGHT") (pintype "passive"))
    )
    (net (code "112") (name "unconnected-(U3-~{XCLR}-Pad8)") (class "Default")
      (node (ref "U3") (pin "8") (pinfunction "~{XCLR}_8") (pintype "input"))
    )
  )
)
